# dmx2rgb.net
KiCad netlist of a schematic drawn in EAGLE
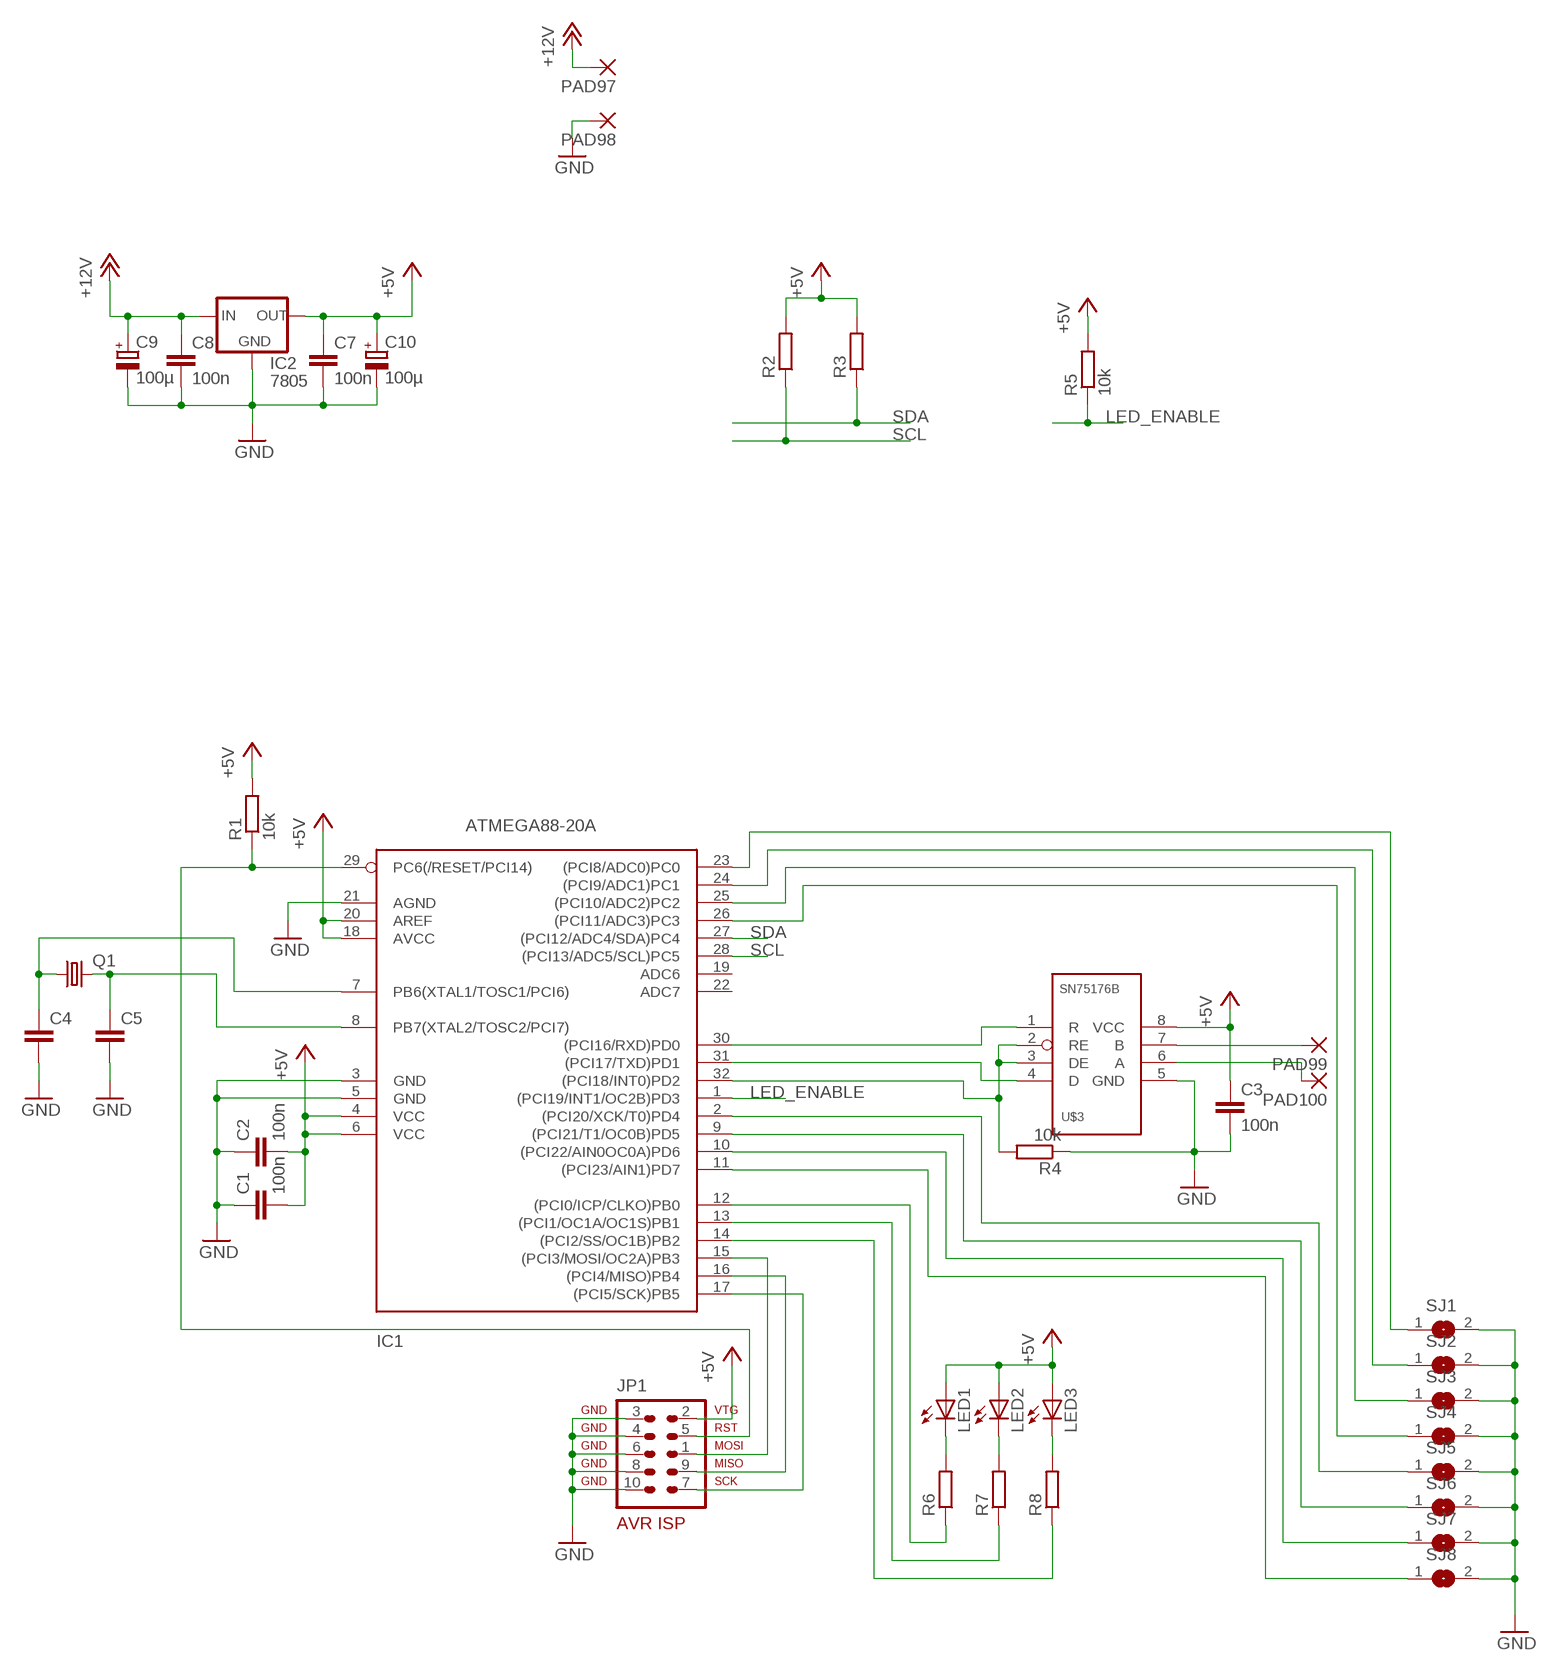
[diagram p0: schematic, sheet 1, part 1 of 2]
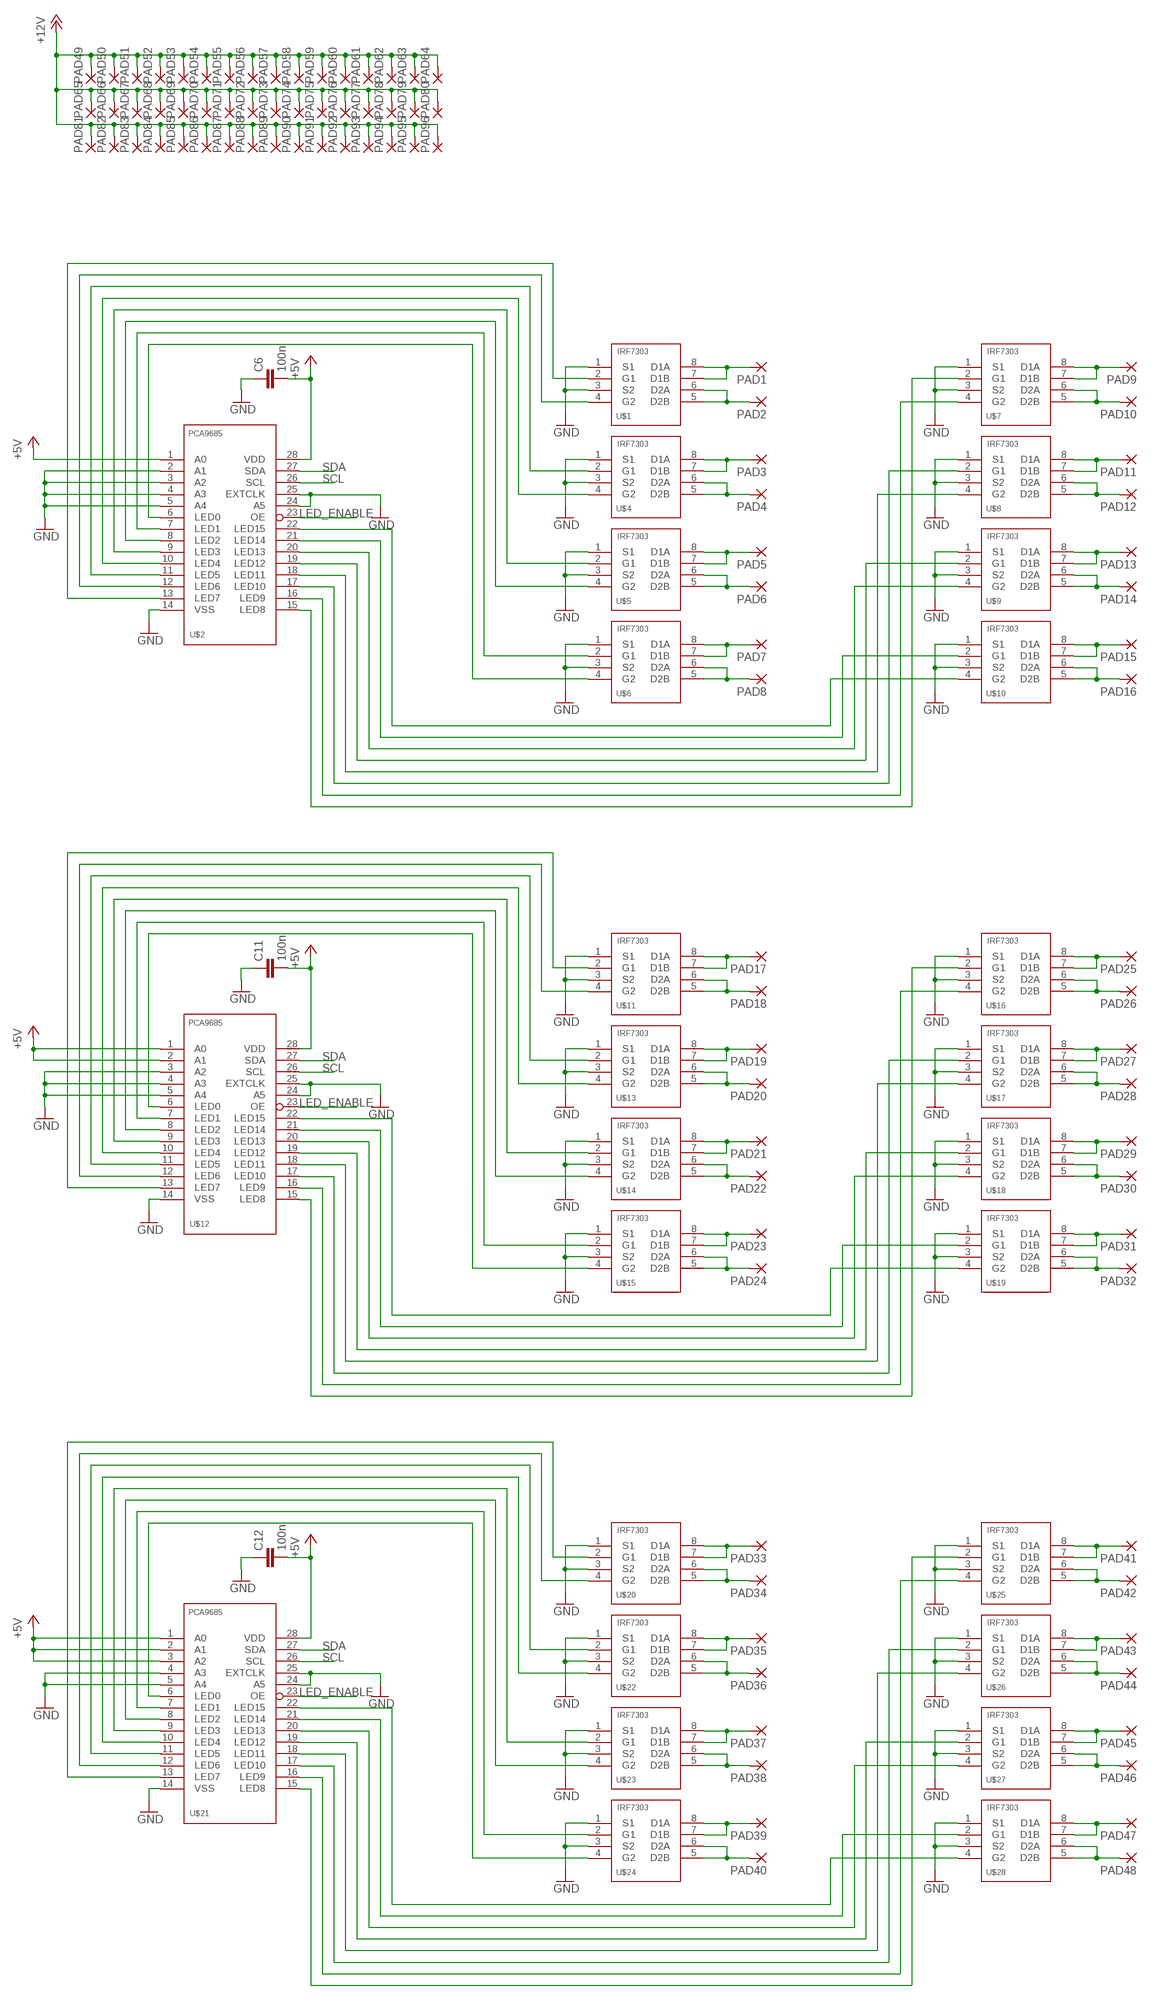
[diagram p1: schematic, sheet 1, part 2 of 2]

(export (version "E")
  (design (tool "Eeschema 10.0.6"))
  (components
    (comp (ref "C1")
      (value "100n")
      (footprint "eagle-import:CHIP_0805")
      (libsource (lib "eagle-import") (part "C0805"))
    )
    (comp (ref "C2")
      (value "100n")
      (footprint "eagle-import:CHIP_0805")
      (libsource (lib "eagle-import") (part "C0805"))
    )
    (comp (ref "C3")
      (value "100n")
      (footprint "eagle-import:CHIP_0805")
      (libsource (lib "eagle-import") (part "C0805"))
    )
    (comp (ref "C4")
      (value "C0805")
      (footprint "eagle-import:CHIP_0805")
      (libsource (lib "eagle-import") (part "C0805"))
    )
    (comp (ref "C5")
      (value "C0805")
      (footprint "eagle-import:CHIP_0805")
      (libsource (lib "eagle-import") (part "C0805"))
    )
    (comp (ref "C6")
      (value "100n")
      (footprint "eagle-import:CHIP_0805")
      (libsource (lib "eagle-import") (part "C0805"))
    )
    (comp (ref "C7")
      (value "100n")
      (footprint "eagle-import:CHIP_0805")
      (libsource (lib "eagle-import") (part "C0805"))
    )
    (comp (ref "C8")
      (value "100n")
      (footprint "eagle-import:CHIP_0805")
      (libsource (lib "eagle-import") (part "C0805"))
    )
    (comp (ref "C9")
      (value "100µ")
      (footprint "eagle-import:E2,5-7")
      (libsource (lib "eagle-import") (part "CPOL-EUE2.5-7"))
    )
    (comp (ref "C10")
      (value "100µ")
      (footprint "eagle-import:E2,5-7")
      (libsource (lib "eagle-import") (part "CPOL-EUE2.5-7"))
    )
    (comp (ref "C11")
      (value "100n")
      (footprint "eagle-import:CHIP_0805")
      (libsource (lib "eagle-import") (part "C0805"))
    )
    (comp (ref "C12")
      (value "100n")
      (footprint "eagle-import:CHIP_0805")
      (libsource (lib "eagle-import") (part "C0805"))
    )
    (comp (ref "IC1")
      (value "ATMEGA88-20A")
      (footprint "eagle-import:TQFP32-08")
      (libsource (lib "eagle-import") (part "ATMEGA88A-20"))
    )
    (comp (ref "IC2")
      (value "7805")
      (footprint "eagle-import:78LXX")
      (libsource (lib "eagle-import") (part "78LXX"))
    )
    (comp (ref "JP1")
      (value "AVR-ISP-10")
      (footprint "eagle-import:AVR-ISP-10")
      (libsource (lib "eagle-import") (part "AVR-ISP-10"))
    )
    (comp (ref "LED1")
      (value "LEDCHIPLED_0805")
      (footprint "eagle-import:CHIPLED_0805")
      (libsource (lib "eagle-import") (part "LEDCHIPLED_0805"))
    )
    (comp (ref "LED2")
      (value "LEDCHIPLED_0805")
      (footprint "eagle-import:CHIPLED_0805")
      (libsource (lib "eagle-import") (part "LEDCHIPLED_0805"))
    )
    (comp (ref "LED3")
      (value "LEDCHIPLED_0805")
      (footprint "eagle-import:CHIPLED_0805")
      (libsource (lib "eagle-import") (part "LEDCHIPLED_0805"))
    )
    (comp (ref "PAD1")
      (value "SMD_PAD_LONG")
      (footprint "eagle-import:SMD_PAD_LONG")
      (libsource (lib "eagle-import") (part "SMD_PAD_LONG"))
    )
    (comp (ref "PAD2")
      (value "SMD_PAD_LONG")
      (footprint "eagle-import:SMD_PAD_LONG")
      (libsource (lib "eagle-import") (part "SMD_PAD_LONG"))
    )
    (comp (ref "PAD3")
      (value "SMD_PAD_LONG")
      (footprint "eagle-import:SMD_PAD_LONG")
      (libsource (lib "eagle-import") (part "SMD_PAD_LONG"))
    )
    (comp (ref "PAD4")
      (value "SMD_PAD_LONG")
      (footprint "eagle-import:SMD_PAD_LONG")
      (libsource (lib "eagle-import") (part "SMD_PAD_LONG"))
    )
    (comp (ref "PAD5")
      (value "SMD_PAD_LONG")
      (footprint "eagle-import:SMD_PAD_LONG")
      (libsource (lib "eagle-import") (part "SMD_PAD_LONG"))
    )
    (comp (ref "PAD6")
      (value "SMD_PAD_LONG")
      (footprint "eagle-import:SMD_PAD_LONG")
      (libsource (lib "eagle-import") (part "SMD_PAD_LONG"))
    )
    (comp (ref "PAD7")
      (value "SMD_PAD_LONG")
      (footprint "eagle-import:SMD_PAD_LONG")
      (libsource (lib "eagle-import") (part "SMD_PAD_LONG"))
    )
    (comp (ref "PAD8")
      (value "SMD_PAD_LONG")
      (footprint "eagle-import:SMD_PAD_LONG")
      (libsource (lib "eagle-import") (part "SMD_PAD_LONG"))
    )
    (comp (ref "PAD9")
      (value "SMD_PAD_LONG")
      (footprint "eagle-import:SMD_PAD_LONG")
      (libsource (lib "eagle-import") (part "SMD_PAD_LONG"))
    )
    (comp (ref "PAD10")
      (value "SMD_PAD_LONG")
      (footprint "eagle-import:SMD_PAD_LONG")
      (libsource (lib "eagle-import") (part "SMD_PAD_LONG"))
    )
    (comp (ref "PAD11")
      (value "SMD_PAD_LONG")
      (footprint "eagle-import:SMD_PAD_LONG")
      (libsource (lib "eagle-import") (part "SMD_PAD_LONG"))
    )
    (comp (ref "PAD12")
      (value "SMD_PAD_LONG")
      (footprint "eagle-import:SMD_PAD_LONG")
      (libsource (lib "eagle-import") (part "SMD_PAD_LONG"))
    )
    (comp (ref "PAD13")
      (value "SMD_PAD_LONG")
      (footprint "eagle-import:SMD_PAD_LONG")
      (libsource (lib "eagle-import") (part "SMD_PAD_LONG"))
    )
    (comp (ref "PAD14")
      (value "SMD_PAD_LONG")
      (footprint "eagle-import:SMD_PAD_LONG")
      (libsource (lib "eagle-import") (part "SMD_PAD_LONG"))
    )
    (comp (ref "PAD15")
      (value "SMD_PAD_LONG")
      (footprint "eagle-import:SMD_PAD_LONG")
      (libsource (lib "eagle-import") (part "SMD_PAD_LONG"))
    )
    (comp (ref "PAD16")
      (value "SMD_PAD_LONG")
      (footprint "eagle-import:SMD_PAD_LONG")
      (libsource (lib "eagle-import") (part "SMD_PAD_LONG"))
    )
    (comp (ref "PAD17")
      (value "SMD_PAD_LONG")
      (footprint "eagle-import:SMD_PAD_LONG")
      (libsource (lib "eagle-import") (part "SMD_PAD_LONG"))
    )
    (comp (ref "PAD18")
      (value "SMD_PAD_LONG")
      (footprint "eagle-import:SMD_PAD_LONG")
      (libsource (lib "eagle-import") (part "SMD_PAD_LONG"))
    )
    (comp (ref "PAD19")
      (value "SMD_PAD_LONG")
      (footprint "eagle-import:SMD_PAD_LONG")
      (libsource (lib "eagle-import") (part "SMD_PAD_LONG"))
    )
    (comp (ref "PAD20")
      (value "SMD_PAD_LONG")
      (footprint "eagle-import:SMD_PAD_LONG")
      (libsource (lib "eagle-import") (part "SMD_PAD_LONG"))
    )
    (comp (ref "PAD21")
      (value "SMD_PAD_LONG")
      (footprint "eagle-import:SMD_PAD_LONG")
      (libsource (lib "eagle-import") (part "SMD_PAD_LONG"))
    )
    (comp (ref "PAD22")
      (value "SMD_PAD_LONG")
      (footprint "eagle-import:SMD_PAD_LONG")
      (libsource (lib "eagle-import") (part "SMD_PAD_LONG"))
    )
    (comp (ref "PAD23")
      (value "SMD_PAD_LONG")
      (footprint "eagle-import:SMD_PAD_LONG")
      (libsource (lib "eagle-import") (part "SMD_PAD_LONG"))
    )
    (comp (ref "PAD24")
      (value "SMD_PAD_LONG")
      (footprint "eagle-import:SMD_PAD_LONG")
      (libsource (lib "eagle-import") (part "SMD_PAD_LONG"))
    )
    (comp (ref "PAD25")
      (value "SMD_PAD_LONG")
      (footprint "eagle-import:SMD_PAD_LONG")
      (libsource (lib "eagle-import") (part "SMD_PAD_LONG"))
    )
    (comp (ref "PAD26")
      (value "SMD_PAD_LONG")
      (footprint "eagle-import:SMD_PAD_LONG")
      (libsource (lib "eagle-import") (part "SMD_PAD_LONG"))
    )
    (comp (ref "PAD27")
      (value "SMD_PAD_LONG")
      (footprint "eagle-import:SMD_PAD_LONG")
      (libsource (lib "eagle-import") (part "SMD_PAD_LONG"))
    )
    (comp (ref "PAD28")
      (value "SMD_PAD_LONG")
      (footprint "eagle-import:SMD_PAD_LONG")
      (libsource (lib "eagle-import") (part "SMD_PAD_LONG"))
    )
    (comp (ref "PAD29")
      (value "SMD_PAD_LONG")
      (footprint "eagle-import:SMD_PAD_LONG")
      (libsource (lib "eagle-import") (part "SMD_PAD_LONG"))
    )
    (comp (ref "PAD30")
      (value "SMD_PAD_LONG")
      (footprint "eagle-import:SMD_PAD_LONG")
      (libsource (lib "eagle-import") (part "SMD_PAD_LONG"))
    )
    (comp (ref "PAD31")
      (value "SMD_PAD_LONG")
      (footprint "eagle-import:SMD_PAD_LONG")
      (libsource (lib "eagle-import") (part "SMD_PAD_LONG"))
    )
    (comp (ref "PAD32")
      (value "SMD_PAD_LONG")
      (footprint "eagle-import:SMD_PAD_LONG")
      (libsource (lib "eagle-import") (part "SMD_PAD_LONG"))
    )
    (comp (ref "PAD33")
      (value "SMD_PAD_LONG")
      (footprint "eagle-import:SMD_PAD_LONG")
      (libsource (lib "eagle-import") (part "SMD_PAD_LONG"))
    )
    (comp (ref "PAD34")
      (value "SMD_PAD_LONG")
      (footprint "eagle-import:SMD_PAD_LONG")
      (libsource (lib "eagle-import") (part "SMD_PAD_LONG"))
    )
    (comp (ref "PAD35")
      (value "SMD_PAD_LONG")
      (footprint "eagle-import:SMD_PAD_LONG")
      (libsource (lib "eagle-import") (part "SMD_PAD_LONG"))
    )
    (comp (ref "PAD36")
      (value "SMD_PAD_LONG")
      (footprint "eagle-import:SMD_PAD_LONG")
      (libsource (lib "eagle-import") (part "SMD_PAD_LONG"))
    )
    (comp (ref "PAD37")
      (value "SMD_PAD_LONG")
      (footprint "eagle-import:SMD_PAD_LONG")
      (libsource (lib "eagle-import") (part "SMD_PAD_LONG"))
    )
    (comp (ref "PAD38")
      (value "SMD_PAD_LONG")
      (footprint "eagle-import:SMD_PAD_LONG")
      (libsource (lib "eagle-import") (part "SMD_PAD_LONG"))
    )
    (comp (ref "PAD39")
      (value "SMD_PAD_LONG")
      (footprint "eagle-import:SMD_PAD_LONG")
      (libsource (lib "eagle-import") (part "SMD_PAD_LONG"))
    )
    (comp (ref "PAD40")
      (value "SMD_PAD_LONG")
      (footprint "eagle-import:SMD_PAD_LONG")
      (libsource (lib "eagle-import") (part "SMD_PAD_LONG"))
    )
    (comp (ref "PAD41")
      (value "SMD_PAD_LONG")
      (footprint "eagle-import:SMD_PAD_LONG")
      (libsource (lib "eagle-import") (part "SMD_PAD_LONG"))
    )
    (comp (ref "PAD42")
      (value "SMD_PAD_LONG")
      (footprint "eagle-import:SMD_PAD_LONG")
      (libsource (lib "eagle-import") (part "SMD_PAD_LONG"))
    )
    (comp (ref "PAD43")
      (value "SMD_PAD_LONG")
      (footprint "eagle-import:SMD_PAD_LONG")
      (libsource (lib "eagle-import") (part "SMD_PAD_LONG"))
    )
    (comp (ref "PAD44")
      (value "SMD_PAD_LONG")
      (footprint "eagle-import:SMD_PAD_LONG")
      (libsource (lib "eagle-import") (part "SMD_PAD_LONG"))
    )
    (comp (ref "PAD45")
      (value "SMD_PAD_LONG")
      (footprint "eagle-import:SMD_PAD_LONG")
      (libsource (lib "eagle-import") (part "SMD_PAD_LONG"))
    )
    (comp (ref "PAD46")
      (value "SMD_PAD_LONG")
      (footprint "eagle-import:SMD_PAD_LONG")
      (libsource (lib "eagle-import") (part "SMD_PAD_LONG"))
    )
    (comp (ref "PAD47")
      (value "SMD_PAD_LONG")
      (footprint "eagle-import:SMD_PAD_LONG")
      (libsource (lib "eagle-import") (part "SMD_PAD_LONG"))
    )
    (comp (ref "PAD48")
      (value "SMD_PAD_LONG")
      (footprint "eagle-import:SMD_PAD_LONG")
      (libsource (lib "eagle-import") (part "SMD_PAD_LONG"))
    )
    (comp (ref "PAD49")
      (value "SMD_PAD_LONG")
      (footprint "eagle-import:SMD_PAD_LONG")
      (libsource (lib "eagle-import") (part "SMD_PAD_LONG"))
    )
    (comp (ref "PAD50")
      (value "SMD_PAD_LONG")
      (footprint "eagle-import:SMD_PAD_LONG")
      (libsource (lib "eagle-import") (part "SMD_PAD_LONG"))
    )
    (comp (ref "PAD51")
      (value "SMD_PAD_LONG")
      (footprint "eagle-import:SMD_PAD_LONG")
      (libsource (lib "eagle-import") (part "SMD_PAD_LONG"))
    )
    (comp (ref "PAD52")
      (value "SMD_PAD_LONG")
      (footprint "eagle-import:SMD_PAD_LONG")
      (libsource (lib "eagle-import") (part "SMD_PAD_LONG"))
    )
    (comp (ref "PAD53")
      (value "SMD_PAD_LONG")
      (footprint "eagle-import:SMD_PAD_LONG")
      (libsource (lib "eagle-import") (part "SMD_PAD_LONG"))
    )
    (comp (ref "PAD54")
      (value "SMD_PAD_LONG")
      (footprint "eagle-import:SMD_PAD_LONG")
      (libsource (lib "eagle-import") (part "SMD_PAD_LONG"))
    )
    (comp (ref "PAD55")
      (value "SMD_PAD_LONG")
      (footprint "eagle-import:SMD_PAD_LONG")
      (libsource (lib "eagle-import") (part "SMD_PAD_LONG"))
    )
    (comp (ref "PAD56")
      (value "SMD_PAD_LONG")
      (footprint "eagle-import:SMD_PAD_LONG")
      (libsource (lib "eagle-import") (part "SMD_PAD_LONG"))
    )
    (comp (ref "PAD57")
      (value "SMD_PAD_LONG")
      (footprint "eagle-import:SMD_PAD_LONG")
      (libsource (lib "eagle-import") (part "SMD_PAD_LONG"))
    )
    (comp (ref "PAD58")
      (value "SMD_PAD_LONG")
      (footprint "eagle-import:SMD_PAD_LONG")
      (libsource (lib "eagle-import") (part "SMD_PAD_LONG"))
    )
    (comp (ref "PAD59")
      (value "SMD_PAD_LONG")
      (footprint "eagle-import:SMD_PAD_LONG")
      (libsource (lib "eagle-import") (part "SMD_PAD_LONG"))
    )
    (comp (ref "PAD60")
      (value "SMD_PAD_LONG")
      (footprint "eagle-import:SMD_PAD_LONG")
      (libsource (lib "eagle-import") (part "SMD_PAD_LONG"))
    )
    (comp (ref "PAD61")
      (value "SMD_PAD_LONG")
      (footprint "eagle-import:SMD_PAD_LONG")
      (libsource (lib "eagle-import") (part "SMD_PAD_LONG"))
    )
    (comp (ref "PAD62")
      (value "SMD_PAD_LONG")
      (footprint "eagle-import:SMD_PAD_LONG")
      (libsource (lib "eagle-import") (part "SMD_PAD_LONG"))
    )
    (comp (ref "PAD63")
      (value "SMD_PAD_LONG")
      (footprint "eagle-import:SMD_PAD_LONG")
      (libsource (lib "eagle-import") (part "SMD_PAD_LONG"))
    )
    (comp (ref "PAD64")
      (value "SMD_PAD_LONG")
      (footprint "eagle-import:SMD_PAD_LONG")
      (libsource (lib "eagle-import") (part "SMD_PAD_LONG"))
    )
    (comp (ref "PAD65")
      (value "SMD_PAD_LONG")
      (footprint "eagle-import:SMD_PAD_LONG")
      (libsource (lib "eagle-import") (part "SMD_PAD_LONG"))
    )
    (comp (ref "PAD66")
      (value "SMD_PAD_LONG")
      (footprint "eagle-import:SMD_PAD_LONG")
      (libsource (lib "eagle-import") (part "SMD_PAD_LONG"))
    )
    (comp (ref "PAD67")
      (value "SMD_PAD_LONG")
      (footprint "eagle-import:SMD_PAD_LONG")
      (libsource (lib "eagle-import") (part "SMD_PAD_LONG"))
    )
    (comp (ref "PAD68")
      (value "SMD_PAD_LONG")
      (footprint "eagle-import:SMD_PAD_LONG")
      (libsource (lib "eagle-import") (part "SMD_PAD_LONG"))
    )
    (comp (ref "PAD69")
      (value "SMD_PAD_LONG")
      (footprint "eagle-import:SMD_PAD_LONG")
      (libsource (lib "eagle-import") (part "SMD_PAD_LONG"))
    )
    (comp (ref "PAD70")
      (value "SMD_PAD_LONG")
      (footprint "eagle-import:SMD_PAD_LONG")
      (libsource (lib "eagle-import") (part "SMD_PAD_LONG"))
    )
    (comp (ref "PAD71")
      (value "SMD_PAD_LONG")
      (footprint "eagle-import:SMD_PAD_LONG")
      (libsource (lib "eagle-import") (part "SMD_PAD_LONG"))
    )
    (comp (ref "PAD72")
      (value "SMD_PAD_LONG")
      (footprint "eagle-import:SMD_PAD_LONG")
      (libsource (lib "eagle-import") (part "SMD_PAD_LONG"))
    )
    (comp (ref "PAD73")
      (value "SMD_PAD_LONG")
      (footprint "eagle-import:SMD_PAD_LONG")
      (libsource (lib "eagle-import") (part "SMD_PAD_LONG"))
    )
    (comp (ref "PAD74")
      (value "SMD_PAD_LONG")
      (footprint "eagle-import:SMD_PAD_LONG")
      (libsource (lib "eagle-import") (part "SMD_PAD_LONG"))
    )
    (comp (ref "PAD75")
      (value "SMD_PAD_LONG")
      (footprint "eagle-import:SMD_PAD_LONG")
      (libsource (lib "eagle-import") (part "SMD_PAD_LONG"))
    )
    (comp (ref "PAD76")
      (value "SMD_PAD_LONG")
      (footprint "eagle-import:SMD_PAD_LONG")
      (libsource (lib "eagle-import") (part "SMD_PAD_LONG"))
    )
    (comp (ref "PAD77")
      (value "SMD_PAD_LONG")
      (footprint "eagle-import:SMD_PAD_LONG")
      (libsource (lib "eagle-import") (part "SMD_PAD_LONG"))
    )
    (comp (ref "PAD78")
      (value "SMD_PAD_LONG")
      (footprint "eagle-import:SMD_PAD_LONG")
      (libsource (lib "eagle-import") (part "SMD_PAD_LONG"))
    )
    (comp (ref "PAD79")
      (value "SMD_PAD_LONG")
      (footprint "eagle-import:SMD_PAD_LONG")
      (libsource (lib "eagle-import") (part "SMD_PAD_LONG"))
    )
    (comp (ref "PAD80")
      (value "SMD_PAD_LONG")
      (footprint "eagle-import:SMD_PAD_LONG")
      (libsource (lib "eagle-import") (part "SMD_PAD_LONG"))
    )
    (comp (ref "PAD81")
      (value "SMD_PAD_LONG")
      (footprint "eagle-import:SMD_PAD_LONG")
      (libsource (lib "eagle-import") (part "SMD_PAD_LONG"))
    )
    (comp (ref "PAD82")
      (value "SMD_PAD_LONG")
      (footprint "eagle-import:SMD_PAD_LONG")
      (libsource (lib "eagle-import") (part "SMD_PAD_LONG"))
    )
    (comp (ref "PAD83")
      (value "SMD_PAD_LONG")
      (footprint "eagle-import:SMD_PAD_LONG")
      (libsource (lib "eagle-import") (part "SMD_PAD_LONG"))
    )
    (comp (ref "PAD84")
      (value "SMD_PAD_LONG")
      (footprint "eagle-import:SMD_PAD_LONG")
      (libsource (lib "eagle-import") (part "SMD_PAD_LONG"))
    )
    (comp (ref "PAD85")
      (value "SMD_PAD_LONG")
      (footprint "eagle-import:SMD_PAD_LONG")
      (libsource (lib "eagle-import") (part "SMD_PAD_LONG"))
    )
    (comp (ref "PAD86")
      (value "SMD_PAD_LONG")
      (footprint "eagle-import:SMD_PAD_LONG")
      (libsource (lib "eagle-import") (part "SMD_PAD_LONG"))
    )
    (comp (ref "PAD87")
      (value "SMD_PAD_LONG")
      (footprint "eagle-import:SMD_PAD_LONG")
      (libsource (lib "eagle-import") (part "SMD_PAD_LONG"))
    )
    (comp (ref "PAD88")
      (value "SMD_PAD_LONG")
      (footprint "eagle-import:SMD_PAD_LONG")
      (libsource (lib "eagle-import") (part "SMD_PAD_LONG"))
    )
    (comp (ref "PAD89")
      (value "SMD_PAD_LONG")
      (footprint "eagle-import:SMD_PAD_LONG")
      (libsource (lib "eagle-import") (part "SMD_PAD_LONG"))
    )
    (comp (ref "PAD90")
      (value "SMD_PAD_LONG")
      (footprint "eagle-import:SMD_PAD_LONG")
      (libsource (lib "eagle-import") (part "SMD_PAD_LONG"))
    )
    (comp (ref "PAD91")
      (value "SMD_PAD_LONG")
      (footprint "eagle-import:SMD_PAD_LONG")
      (libsource (lib "eagle-import") (part "SMD_PAD_LONG"))
    )
    (comp (ref "PAD92")
      (value "SMD_PAD_LONG")
      (footprint "eagle-import:SMD_PAD_LONG")
      (libsource (lib "eagle-import") (part "SMD_PAD_LONG"))
    )
    (comp (ref "PAD93")
      (value "SMD_PAD_LONG")
      (footprint "eagle-import:SMD_PAD_LONG")
      (libsource (lib "eagle-import") (part "SMD_PAD_LONG"))
    )
    (comp (ref "PAD94")
      (value "SMD_PAD_LONG")
      (footprint "eagle-import:SMD_PAD_LONG")
      (libsource (lib "eagle-import") (part "SMD_PAD_LONG"))
    )
    (comp (ref "PAD95")
      (value "SMD_PAD_LONG")
      (footprint "eagle-import:SMD_PAD_LONG")
      (libsource (lib "eagle-import") (part "SMD_PAD_LONG"))
    )
    (comp (ref "PAD96")
      (value "SMD_PAD_LONG")
      (footprint "eagle-import:SMD_PAD_LONG")
      (libsource (lib "eagle-import") (part "SMD_PAD_LONG"))
    )
    (comp (ref "PAD97")
      (value "SMD5")
      (footprint "eagle-import:SMD2,54-5,08")
      (libsource (lib "eagle-import") (part "SMD5"))
    )
    (comp (ref "PAD98")
      (value "SMD5")
      (footprint "eagle-import:SMD2,54-5,08")
      (libsource (lib "eagle-import") (part "SMD5"))
    )
    (comp (ref "PAD99")
      (value "SMD_PAD_LONG")
      (footprint "eagle-import:SMD_PAD_LONG")
      (libsource (lib "eagle-import") (part "SMD_PAD_LONG"))
    )
    (comp (ref "PAD100")
      (value "SMD_PAD_LONG")
      (footprint "eagle-import:SMD_PAD_LONG")
      (libsource (lib "eagle-import") (part "SMD_PAD_LONG"))
    )
    (comp (ref "Q1")
      (value "CRYSTAL49")
      (footprint "eagle-import:HC49_S")
      (libsource (lib "eagle-import") (part "CRYSTAL49"))
    )
    (comp (ref "R1")
      (value "10k")
      (footprint "eagle-import:CHIP_0805")
      (libsource (lib "eagle-import") (part "R0805"))
    )
    (comp (ref "R2")
      (value "R0805")
      (footprint "eagle-import:CHIP_0805")
      (libsource (lib "eagle-import") (part "R0805"))
    )
    (comp (ref "R3")
      (value "R0805")
      (footprint "eagle-import:CHIP_0805")
      (libsource (lib "eagle-import") (part "R0805"))
    )
    (comp (ref "R4")
      (value "10k")
      (footprint "eagle-import:CHIP_0805")
      (libsource (lib "eagle-import") (part "R0805"))
    )
    (comp (ref "R5")
      (value "10k")
      (footprint "eagle-import:CHIP_0805")
      (libsource (lib "eagle-import") (part "R0805"))
    )
    (comp (ref "R6")
      (value "R0805")
      (footprint "eagle-import:CHIP_0805")
      (libsource (lib "eagle-import") (part "R0805"))
    )
    (comp (ref "R7")
      (value "R0805")
      (footprint "eagle-import:CHIP_0805")
      (libsource (lib "eagle-import") (part "R0805"))
    )
    (comp (ref "R8")
      (value "R0805")
      (footprint "eagle-import:CHIP_0805")
      (libsource (lib "eagle-import") (part "R0805"))
    )
    (comp (ref "SJ1") (value "SJ") (footprint "eagle-import:SJ") (libsource (lib "eagle-import") (part "SJ")))
    (comp (ref "SJ2") (value "SJ") (footprint "eagle-import:SJ") (libsource (lib "eagle-import") (part "SJ")))
    (comp (ref "SJ3") (value "SJ") (footprint "eagle-import:SJ") (libsource (lib "eagle-import") (part "SJ")))
    (comp (ref "SJ4") (value "SJ") (footprint "eagle-import:SJ") (libsource (lib "eagle-import") (part "SJ")))
    (comp (ref "SJ5") (value "SJ") (footprint "eagle-import:SJ") (libsource (lib "eagle-import") (part "SJ")))
    (comp (ref "SJ6") (value "SJ") (footprint "eagle-import:SJ") (libsource (lib "eagle-import") (part "SJ")))
    (comp (ref "SJ7") (value "SJ") (footprint "eagle-import:SJ") (libsource (lib "eagle-import") (part "SJ")))
    (comp (ref "SJ8") (value "SJ") (footprint "eagle-import:SJ") (libsource (lib "eagle-import") (part "SJ")))
    (comp (ref "U$1")
      (value "IRF7303")
      (footprint "eagle-import:SO8")
      (libsource (lib "eagle-import") (part "IRF7303"))
    )
    (comp (ref "U$2")
      (value "PCA9685")
      (footprint "eagle-import:TSSOP28")
      (libsource (lib "eagle-import") (part "PCA9685"))
    )
    (comp (ref "U$3")
      (value "SN75176B")
      (footprint "eagle-import:SO8")
      (libsource (lib "eagle-import") (part "SN75176B"))
    )
    (comp (ref "U$4")
      (value "IRF7303")
      (footprint "eagle-import:SO8")
      (libsource (lib "eagle-import") (part "IRF7303"))
    )
    (comp (ref "U$5")
      (value "IRF7303")
      (footprint "eagle-import:SO8")
      (libsource (lib "eagle-import") (part "IRF7303"))
    )
    (comp (ref "U$6")
      (value "IRF7303")
      (footprint "eagle-import:SO8")
      (libsource (lib "eagle-import") (part "IRF7303"))
    )
    (comp (ref "U$7")
      (value "IRF7303")
      (footprint "eagle-import:SO8")
      (libsource (lib "eagle-import") (part "IRF7303"))
    )
    (comp (ref "U$8")
      (value "IRF7303")
      (footprint "eagle-import:SO8")
      (libsource (lib "eagle-import") (part "IRF7303"))
    )
    (comp (ref "U$9")
      (value "IRF7303")
      (footprint "eagle-import:SO8")
      (libsource (lib "eagle-import") (part "IRF7303"))
    )
    (comp (ref "U$10")
      (value "IRF7303")
      (footprint "eagle-import:SO8")
      (libsource (lib "eagle-import") (part "IRF7303"))
    )
    (comp (ref "U$11")
      (value "IRF7303")
      (footprint "eagle-import:SO8")
      (libsource (lib "eagle-import") (part "IRF7303"))
    )
    (comp (ref "U$12")
      (value "PCA9685")
      (footprint "eagle-import:TSSOP28")
      (libsource (lib "eagle-import") (part "PCA9685"))
    )
    (comp (ref "U$13")
      (value "IRF7303")
      (footprint "eagle-import:SO8")
      (libsource (lib "eagle-import") (part "IRF7303"))
    )
    (comp (ref "U$14")
      (value "IRF7303")
      (footprint "eagle-import:SO8")
      (libsource (lib "eagle-import") (part "IRF7303"))
    )
    (comp (ref "U$15")
      (value "IRF7303")
      (footprint "eagle-import:SO8")
      (libsource (lib "eagle-import") (part "IRF7303"))
    )
    (comp (ref "U$16")
      (value "IRF7303")
      (footprint "eagle-import:SO8")
      (libsource (lib "eagle-import") (part "IRF7303"))
    )
    (comp (ref "U$17")
      (value "IRF7303")
      (footprint "eagle-import:SO8")
      (libsource (lib "eagle-import") (part "IRF7303"))
    )
    (comp (ref "U$18")
      (value "IRF7303")
      (footprint "eagle-import:SO8")
      (libsource (lib "eagle-import") (part "IRF7303"))
    )
    (comp (ref "U$19")
      (value "IRF7303")
      (footprint "eagle-import:SO8")
      (libsource (lib "eagle-import") (part "IRF7303"))
    )
    (comp (ref "U$20")
      (value "IRF7303")
      (footprint "eagle-import:SO8")
      (libsource (lib "eagle-import") (part "IRF7303"))
    )
    (comp (ref "U$21")
      (value "PCA9685")
      (footprint "eagle-import:TSSOP28")
      (libsource (lib "eagle-import") (part "PCA9685"))
    )
    (comp (ref "U$22")
      (value "IRF7303")
      (footprint "eagle-import:SO8")
      (libsource (lib "eagle-import") (part "IRF7303"))
    )
    (comp (ref "U$23")
      (value "IRF7303")
      (footprint "eagle-import:SO8")
      (libsource (lib "eagle-import") (part "IRF7303"))
    )
    (comp (ref "U$24")
      (value "IRF7303")
      (footprint "eagle-import:SO8")
      (libsource (lib "eagle-import") (part "IRF7303"))
    )
    (comp (ref "U$25")
      (value "IRF7303")
      (footprint "eagle-import:SO8")
      (libsource (lib "eagle-import") (part "IRF7303"))
    )
    (comp (ref "U$26")
      (value "IRF7303")
      (footprint "eagle-import:SO8")
      (libsource (lib "eagle-import") (part "IRF7303"))
    )
    (comp (ref "U$27")
      (value "IRF7303")
      (footprint "eagle-import:SO8")
      (libsource (lib "eagle-import") (part "IRF7303"))
    )
    (comp (ref "U$28")
      (value "IRF7303")
      (footprint "eagle-import:SO8")
      (libsource (lib "eagle-import") (part "IRF7303"))
    )
  )
  (nets
    (net (code "1") (name "+5V") (class "Default")
      (node (ref "C1") (pin "2") (pinfunction "2_2") (pintype "passive"))
      (node (ref "C10") (pin "+") (pinfunction "+_+") (pintype "passive"))
      (node (ref "C11") (pin "2") (pinfunction "2_2") (pintype "passive"))
      (node (ref "C12") (pin "2") (pinfunction "2_2") (pintype "passive"))
      (node (ref "C2") (pin "2") (pinfunction "2_2") (pintype "passive"))
      (node (ref "C3") (pin "1") (pinfunction "1_1") (pintype "passive"))
      (node (ref "C6") (pin "2") (pinfunction "2_2") (pintype "passive"))
      (node (ref "C7") (pin "1") (pinfunction "1_1") (pintype "passive"))
      (node (ref "IC1") (pin "18") (pinfunction "AVCC_18") (pintype "bidirectional"))
      (node (ref "IC1") (pin "20") (pinfunction "AREF_20") (pintype "bidirectional"))
      (node (ref "IC1") (pin "4") (pinfunction "VCC_4") (pintype "power_in"))
      (node (ref "IC1") (pin "6") (pinfunction "VCC_6") (pintype "power_in"))
      (node (ref "IC2") (pin "OUT") (pinfunction "OUT_OUT") (pintype "passive"))
      (node (ref "JP1") (pin "2") (pinfunction "2_2") (pintype "passive"))
      (node (ref "LED1") (pin "A") (pinfunction "A_A") (pintype "passive"))
      (node (ref "LED2") (pin "A") (pinfunction "A_A") (pintype "passive"))
      (node (ref "LED3") (pin "A") (pinfunction "A_A") (pintype "passive"))
      (node (ref "R1") (pin "2") (pinfunction "2_2") (pintype "passive"))
      (node (ref "R2") (pin "2") (pinfunction "2_2") (pintype "passive"))
      (node (ref "R3") (pin "2") (pinfunction "2_2") (pintype "passive"))
      (node (ref "R5") (pin "2") (pinfunction "2_2") (pintype "passive"))
      (node (ref "U$12") (pin "1") (pinfunction "A0_1") (pintype "bidirectional"))
      (node (ref "U$12") (pin "2") (pinfunction "A1_2") (pintype "bidirectional"))
      (node (ref "U$12") (pin "28") (pinfunction "VDD_28") (pintype "bidirectional"))
      (node (ref "U$2") (pin "1") (pinfunction "A0_1") (pintype "bidirectional"))
      (node (ref "U$2") (pin "28") (pinfunction "VDD_28") (pintype "bidirectional"))
      (node (ref "U$21") (pin "1") (pinfunction "A0_1") (pintype "bidirectional"))
      (node (ref "U$21") (pin "2") (pinfunction "A1_2") (pintype "bidirectional"))
      (node (ref "U$21") (pin "28") (pinfunction "VDD_28") (pintype "bidirectional"))
      (node (ref "U$21") (pin "3") (pinfunction "A2_3") (pintype "bidirectional"))
      (node (ref "U$3") (pin "8") (pinfunction "VCC_8") (pintype "bidirectional"))
    )
    (net (code "2") (name "+12V") (class "Default")
      (node (ref "C8") (pin "1") (pinfunction "1_1") (pintype "passive"))
      (node (ref "C9") (pin "+") (pinfunction "+_+") (pintype "passive"))
      (node (ref "IC2") (pin "IN") (pinfunction "IN_IN") (pintype "input"))
      (node (ref "PAD49") (pin "P$1") (pinfunction "P_P$1") (pintype "passive"))
      (node (ref "PAD50") (pin "P$1") (pinfunction "P_P$1") (pintype "passive"))
      (node (ref "PAD51") (pin "P$1") (pinfunction "P_P$1") (pintype "passive"))
      (node (ref "PAD52") (pin "P$1") (pinfunction "P_P$1") (pintype "passive"))
      (node (ref "PAD53") (pin "P$1") (pinfunction "P_P$1") (pintype "passive"))
      (node (ref "PAD54") (pin "P$1") (pinfunction "P_P$1") (pintype "passive"))
      (node (ref "PAD55") (pin "P$1") (pinfunction "P_P$1") (pintype "passive"))
      (node (ref "PAD56") (pin "P$1") (pinfunction "P_P$1") (pintype "passive"))
      (node (ref "PAD57") (pin "P$1") (pinfunction "P_P$1") (pintype "passive"))
      (node (ref "PAD58") (pin "P$1") (pinfunction "P_P$1") (pintype "passive"))
      (node (ref "PAD59") (pin "P$1") (pinfunction "P_P$1") (pintype "passive"))
      (node (ref "PAD60") (pin "P$1") (pinfunction "P_P$1") (pintype "passive"))
      (node (ref "PAD61") (pin "P$1") (pinfunction "P_P$1") (pintype "passive"))
      (node (ref "PAD62") (pin "P$1") (pinfunction "P_P$1") (pintype "passive"))
      (node (ref "PAD63") (pin "P$1") (pinfunction "P_P$1") (pintype "passive"))
      (node (ref "PAD64") (pin "P$1") (pinfunction "P_P$1") (pintype "passive"))
      (node (ref "PAD65") (pin "P$1") (pinfunction "P_P$1") (pintype "passive"))
      (node (ref "PAD66") (pin "P$1") (pinfunction "P_P$1") (pintype "passive"))
      (node (ref "PAD67") (pin "P$1") (pinfunction "P_P$1") (pintype "passive"))
      (node (ref "PAD68") (pin "P$1") (pinfunction "P_P$1") (pintype "passive"))
      (node (ref "PAD69") (pin "P$1") (pinfunction "P_P$1") (pintype "passive"))
      (node (ref "PAD70") (pin "P$1") (pinfunction "P_P$1") (pintype "passive"))
      (node (ref "PAD71") (pin "P$1") (pinfunction "P_P$1") (pintype "passive"))
      (node (ref "PAD72") (pin "P$1") (pinfunction "P_P$1") (pintype "passive"))
      (node (ref "PAD73") (pin "P$1") (pinfunction "P_P$1") (pintype "passive"))
      (node (ref "PAD74") (pin "P$1") (pinfunction "P_P$1") (pintype "passive"))
      (node (ref "PAD75") (pin "P$1") (pinfunction "P_P$1") (pintype "passive"))
      (node (ref "PAD76") (pin "P$1") (pinfunction "P_P$1") (pintype "passive"))
      (node (ref "PAD77") (pin "P$1") (pinfunction "P_P$1") (pintype "passive"))
      (node (ref "PAD78") (pin "P$1") (pinfunction "P_P$1") (pintype "passive"))
      (node (ref "PAD79") (pin "P$1") (pinfunction "P_P$1") (pintype "passive"))
      (node (ref "PAD80") (pin "P$1") (pinfunction "P_P$1") (pintype "passive"))
      (node (ref "PAD81") (pin "P$1") (pinfunction "P_P$1") (pintype "passive"))
      (node (ref "PAD82") (pin "P$1") (pinfunction "P_P$1") (pintype "passive"))
      (node (ref "PAD83") (pin "P$1") (pinfunction "P_P$1") (pintype "passive"))
      (node (ref "PAD84") (pin "P$1") (pinfunction "P_P$1") (pintype "passive"))
      (node (ref "PAD85") (pin "P$1") (pinfunction "P_P$1") (pintype "passive"))
      (node (ref "PAD86") (pin "P$1") (pinfunction "P_P$1") (pintype "passive"))
      (node (ref "PAD87") (pin "P$1") (pinfunction "P_P$1") (pintype "passive"))
      (node (ref "PAD88") (pin "P$1") (pinfunction "P_P$1") (pintype "passive"))
      (node (ref "PAD89") (pin "P$1") (pinfunction "P_P$1") (pintype "passive"))
      (node (ref "PAD90") (pin "P$1") (pinfunction "P_P$1") (pintype "passive"))
      (node (ref "PAD91") (pin "P$1") (pinfunction "P_P$1") (pintype "passive"))
      (node (ref "PAD92") (pin "P$1") (pinfunction "P_P$1") (pintype "passive"))
      (node (ref "PAD93") (pin "P$1") (pinfunction "P_P$1") (pintype "passive"))
      (node (ref "PAD94") (pin "P$1") (pinfunction "P_P$1") (pintype "passive"))
      (node (ref "PAD95") (pin "P$1") (pinfunction "P_P$1") (pintype "passive"))
      (node (ref "PAD96") (pin "P$1") (pinfunction "P_P$1") (pintype "passive"))
      (node (ref "PAD97") (pin "1") (pinfunction "P_1") (pintype "passive"))
    )
    (net (code "3") (name "/LED_ENABLE") (class "Default")
      (node (ref "IC1") (pin "1") (pinfunction "(PCI19/INT1/OC2B)PD3_1") (pintype "bidirectional"))
      (node (ref "R5") (pin "1") (pinfunction "1_1") (pintype "passive"))
      (node (ref "U$12") (pin "23") (pinfunction "OE_23") (pintype "input"))
      (node (ref "U$2") (pin "23") (pinfunction "OE_23") (pintype "input"))
      (node (ref "U$21") (pin "23") (pinfunction "OE_23") (pintype "input"))
    )
    (net (code "4") (name "/SCL") (class "Default")
      (node (ref "IC1") (pin "28") (pinfunction "(PCI13/ADC5/SCL)PC5_28") (pintype "bidirectional"))
      (node (ref "R2") (pin "1") (pinfunction "1_1") (pintype "passive"))
      (node (ref "U$12") (pin "26") (pinfunction "SCL_26") (pintype "bidirectional"))
      (node (ref "U$2") (pin "26") (pinfunction "SCL_26") (pintype "bidirectional"))
      (node (ref "U$21") (pin "26") (pinfunction "SCL_26") (pintype "bidirectional"))
    )
    (net (code "5") (name "/SDA") (class "Default")
      (node (ref "IC1") (pin "27") (pinfunction "(PCI12/ADC4/SDA)PC4_27") (pintype "bidirectional"))
      (node (ref "R3") (pin "1") (pinfunction "1_1") (pintype "passive"))
      (node (ref "U$12") (pin "27") (pinfunction "SDA_27") (pintype "bidirectional"))
      (node (ref "U$2") (pin "27") (pinfunction "SDA_27") (pintype "bidirectional"))
      (node (ref "U$21") (pin "27") (pinfunction "SDA_27") (pintype "bidirectional"))
    )
    (net (code "6") (name "GND") (class "Default")
      (node (ref "C1") (pin "1") (pinfunction "1_1") (pintype "passive"))
      (node (ref "C10") (pin "-") (pinfunction "-_-") (pintype "passive"))
      (node (ref "C11") (pin "1") (pinfunction "1_1") (pintype "passive"))
      (node (ref "C12") (pin "1") (pinfunction "1_1") (pintype "passive"))
      (node (ref "C2") (pin "1") (pinfunction "1_1") (pintype "passive"))
      (node (ref "C3") (pin "2") (pinfunction "2_2") (pintype "passive"))
      (node (ref "C4") (pin "2") (pinfunction "2_2") (pintype "passive"))
      (node (ref "C5") (pin "2") (pinfunction "2_2") (pintype "passive"))
      (node (ref "C6") (pin "1") (pinfunction "1_1") (pintype "passive"))
      (node (ref "C7") (pin "2") (pinfunction "2_2") (pintype "passive"))
      (node (ref "C8") (pin "2") (pinfunction "2_2") (pintype "passive"))
      (node (ref "C9") (pin "-") (pinfunction "-_-") (pintype "passive"))
      (node (ref "IC1") (pin "21") (pinfunction "AGND_21") (pintype "bidirectional"))
      (node (ref "IC1") (pin "3") (pinfunction "GND_3") (pintype "power_in"))
      (node (ref "IC1") (pin "5") (pinfunction "GND_5") (pintype "power_in"))
      (node (ref "IC2") (pin "GND") (pinfunction "GND_GND") (pintype "input"))
      (node (ref "JP1") (pin "10") (pinfunction "10_10") (pintype "passive"))
      (node (ref "JP1") (pin "3") (pinfunction "3_3") (pintype "passive"))
      (node (ref "JP1") (pin "4") (pinfunction "4_4") (pintype "passive"))
      (node (ref "JP1") (pin "6") (pinfunction "6_6") (pintype "passive"))
      (node (ref "JP1") (pin "8") (pinfunction "8_8") (pintype "passive"))
      (node (ref "PAD98") (pin "1") (pinfunction "P_1") (pintype "passive"))
      (node (ref "R4") (pin "1") (pinfunction "1_1") (pintype "passive"))
      (node (ref "SJ1") (pin "2") (pinfunction "2_2") (pintype "passive"))
      (node (ref "SJ2") (pin "2") (pinfunction "2_2") (pintype "passive"))
      (node (ref "SJ3") (pin "2") (pinfunction "2_2") (pintype "passive"))
      (node (ref "SJ4") (pin "2") (pinfunction "2_2") (pintype "passive"))
      (node (ref "SJ5") (pin "2") (pinfunction "2_2") (pintype "passive"))
      (node (ref "SJ6") (pin "2") (pinfunction "2_2") (pintype "passive"))
      (node (ref "SJ7") (pin "2") (pinfunction "2_2") (pintype "passive"))
      (node (ref "SJ8") (pin "2") (pinfunction "2_2") (pintype "passive"))
      (node (ref "U$1") (pin "1") (pinfunction "S1_1") (pintype "input"))
      (node (ref "U$1") (pin "3") (pinfunction "S2_3") (pintype "bidirectional"))
      (node (ref "U$10") (pin "1") (pinfunction "S1_1") (pintype "input"))
      (node (ref "U$10") (pin "3") (pinfunction "S2_3") (pintype "bidirectional"))
      (node (ref "U$11") (pin "1") (pinfunction "S1_1") (pintype "input"))
      (node (ref "U$11") (pin "3") (pinfunction "S2_3") (pintype "bidirectional"))
      (node (ref "U$12") (pin "14") (pinfunction "VSS_14") (pintype "bidirectional"))
      (node (ref "U$12") (pin "24") (pinfunction "A5_24") (pintype "bidirectional"))
      (node (ref "U$12") (pin "25") (pinfunction "EXTCLK_25") (pintype "bidirectional"))
      (node (ref "U$12") (pin "3") (pinfunction "A2_3") (pintype "bidirectional"))
      (node (ref "U$12") (pin "4") (pinfunction "A3_4") (pintype "bidirectional"))
      (node (ref "U$12") (pin "5") (pinfunction "A4_5") (pintype "bidirectional"))
      (node (ref "U$13") (pin "1") (pinfunction "S1_1") (pintype "input"))
      (node (ref "U$13") (pin "3") (pinfunction "S2_3") (pintype "bidirectional"))
      (node (ref "U$14") (pin "1") (pinfunction "S1_1") (pintype "input"))
      (node (ref "U$14") (pin "3") (pinfunction "S2_3") (pintype "bidirectional"))
      (node (ref "U$15") (pin "1") (pinfunction "S1_1") (pintype "input"))
      (node (ref "U$15") (pin "3") (pinfunction "S2_3") (pintype "bidirectional"))
      (node (ref "U$16") (pin "1") (pinfunction "S1_1") (pintype "input"))
      (node (ref "U$16") (pin "3") (pinfunction "S2_3") (pintype "bidirectional"))
      (node (ref "U$17") (pin "1") (pinfunction "S1_1") (pintype "input"))
      (node (ref "U$17") (pin "3") (pinfunction "S2_3") (pintype "bidirectional"))
      (node (ref "U$18") (pin "1") (pinfunction "S1_1") (pintype "input"))
      (node (ref "U$18") (pin "3") (pinfunction "S2_3") (pintype "bidirectional"))
      (node (ref "U$19") (pin "1") (pinfunction "S1_1") (pintype "input"))
      (node (ref "U$19") (pin "3") (pinfunction "S2_3") (pintype "bidirectional"))
      (node (ref "U$2") (pin "14") (pinfunction "VSS_14") (pintype "bidirectional"))
      (node (ref "U$2") (pin "2") (pinfunction "A1_2") (pintype "bidirectional"))
      (node (ref "U$2") (pin "24") (pinfunction "A5_24") (pintype "bidirectional"))
      (node (ref "U$2") (pin "25") (pinfunction "EXTCLK_25") (pintype "bidirectional"))
      (node (ref "U$2") (pin "3") (pinfunction "A2_3") (pintype "bidirectional"))
      (node (ref "U$2") (pin "4") (pinfunction "A3_4") (pintype "bidirectional"))
      (node (ref "U$2") (pin "5") (pinfunction "A4_5") (pintype "bidirectional"))
      (node (ref "U$20") (pin "1") (pinfunction "S1_1") (pintype "input"))
      (node (ref "U$20") (pin "3") (pinfunction "S2_3") (pintype "bidirectional"))
      (node (ref "U$21") (pin "14") (pinfunction "VSS_14") (pintype "bidirectional"))
      (node (ref "U$21") (pin "24") (pinfunction "A5_24") (pintype "bidirectional"))
      (node (ref "U$21") (pin "25") (pinfunction "EXTCLK_25") (pintype "bidirectional"))
      (node (ref "U$21") (pin "4") (pinfunction "A3_4") (pintype "bidirectional"))
      (node (ref "U$21") (pin "5") (pinfunction "A4_5") (pintype "bidirectional"))
      (node (ref "U$22") (pin "1") (pinfunction "S1_1") (pintype "input"))
      (node (ref "U$22") (pin "3") (pinfunction "S2_3") (pintype "bidirectional"))
      (node (ref "U$23") (pin "1") (pinfunction "S1_1") (pintype "input"))
      (node (ref "U$23") (pin "3") (pinfunction "S2_3") (pintype "bidirectional"))
      (node (ref "U$24") (pin "1") (pinfunction "S1_1") (pintype "input"))
      (node (ref "U$24") (pin "3") (pinfunction "S2_3") (pintype "bidirectional"))
      (node (ref "U$25") (pin "1") (pinfunction "S1_1") (pintype "input"))
      (node (ref "U$25") (pin "3") (pinfunction "S2_3") (pintype "bidirectional"))
      (node (ref "U$26") (pin "1") (pinfunction "S1_1") (pintype "input"))
      (node (ref "U$26") (pin "3") (pinfunction "S2_3") (pintype "bidirectional"))
      (node (ref "U$27") (pin "1") (pinfunction "S1_1") (pintype "input"))
      (node (ref "U$27") (pin "3") (pinfunction "S2_3") (pintype "bidirectional"))
      (node (ref "U$28") (pin "1") (pinfunction "S1_1") (pintype "input"))
      (node (ref "U$28") (pin "3") (pinfunction "S2_3") (pintype "bidirectional"))
      (node (ref "U$3") (pin "5") (pinfunction "GND_5") (pintype "bidirectional"))
      (node (ref "U$4") (pin "1") (pinfunction "S1_1") (pintype "input"))
      (node (ref "U$4") (pin "3") (pinfunction "S2_3") (pintype "bidirectional"))
      (node (ref "U$5") (pin "1") (pinfunction "S1_1") (pintype "input"))
      (node (ref "U$5") (pin "3") (pinfunction "S2_3") (pintype "bidirectional"))
      (node (ref "U$6") (pin "1") (pinfunction "S1_1") (pintype "input"))
      (node (ref "U$6") (pin "3") (pinfunction "S2_3") (pintype "bidirectional"))
      (node (ref "U$7") (pin "1") (pinfunction "S1_1") (pintype "input"))
      (node (ref "U$7") (pin "3") (pinfunction "S2_3") (pintype "bidirectional"))
      (node (ref "U$8") (pin "1") (pinfunction "S1_1") (pintype "input"))
      (node (ref "U$8") (pin "3") (pinfunction "S2_3") (pintype "bidirectional"))
      (node (ref "U$9") (pin "1") (pinfunction "S1_1") (pintype "input"))
      (node (ref "U$9") (pin "3") (pinfunction "S2_3") (pintype "bidirectional"))
    )
    (net (code "7") (name "Net-(IC1-(PCI0{slash}ICP{slash}CLKO)PB0)") (class "Default")
      (node (ref "IC1") (pin "12") (pinfunction "(PCI0/ICP/CLKO)PB0_12") (pintype "bidirectional"))
      (node (ref "R6") (pin "1") (pinfunction "1_1") (pintype "passive"))
    )
    (net (code "8") (name "Net-(IC1-(PCI1{slash}OC1A{slash}OC1S)PB1)") (class "Default")
      (node (ref "IC1") (pin "13") (pinfunction "(PCI1/OC1A/OC1S)PB1_13") (pintype "bidirectional"))
      (node (ref "R7") (pin "1") (pinfunction "1_1") (pintype "passive"))
    )
    (net (code "9") (name "Net-(IC1-(PCI2{slash}SS{slash}OC1B)PB2)") (class "Default")
      (node (ref "IC1") (pin "14") (pinfunction "(PCI2/SS/OC1B)PB2_14") (pintype "bidirectional"))
      (node (ref "R8") (pin "1") (pinfunction "1_1") (pintype "passive"))
    )
    (net (code "10") (name "Net-(IC1-(PCI3{slash}MOSI{slash}OC2A)PB3)") (class "Default")
      (node (ref "IC1") (pin "15") (pinfunction "(PCI3/MOSI/OC2A)PB3_15") (pintype "bidirectional"))
      (node (ref "JP1") (pin "1") (pinfunction "1_1") (pintype "passive"))
    )
    (net (code "11") (name "Net-(IC1-(PCI4{slash}MISO)PB4)") (class "Default")
      (node (ref "IC1") (pin "16") (pinfunction "(PCI4/MISO)PB4_16") (pintype "bidirectional"))
      (node (ref "JP1") (pin "9") (pinfunction "9_9") (pintype "passive"))
    )
    (net (code "12") (name "Net-(IC1-(PCI5{slash}SCK)PB5)") (class "Default")
      (node (ref "IC1") (pin "17") (pinfunction "(PCI5/SCK)PB5_17") (pintype "bidirectional"))
      (node (ref "JP1") (pin "7") (pinfunction "7_7") (pintype "passive"))
    )
    (net (code "13") (name "Net-(IC1-(PCI8{slash}ADC0)PC0)") (class "Default")
      (node (ref "IC1") (pin "23") (pinfunction "(PCI8/ADC0)PC0_23") (pintype "bidirectional"))
      (node (ref "SJ1") (pin "1") (pinfunction "1_1") (pintype "passive"))
    )
    (net (code "14") (name "Net-(IC1-(PCI9{slash}ADC1)PC1)") (class "Default")
      (node (ref "IC1") (pin "24") (pinfunction "(PCI9/ADC1)PC1_24") (pintype "bidirectional"))
      (node (ref "SJ2") (pin "1") (pinfunction "1_1") (pintype "passive"))
    )
    (net (code "15") (name "Net-(IC1-(PCI10{slash}ADC2)PC2)") (class "Default")
      (node (ref "IC1") (pin "25") (pinfunction "(PCI10/ADC2)PC2_25") (pintype "bidirectional"))
      (node (ref "SJ3") (pin "1") (pinfunction "1_1") (pintype "passive"))
    )
    (net (code "16") (name "Net-(IC1-(PCI11{slash}ADC3)PC3)") (class "Default")
      (node (ref "IC1") (pin "26") (pinfunction "(PCI11/ADC3)PC3_26") (pintype "bidirectional"))
      (node (ref "SJ4") (pin "1") (pinfunction "1_1") (pintype "passive"))
    )
    (net (code "17") (name "Net-(IC1-(PCI16{slash}RXD)PD0)") (class "Default")
      (node (ref "IC1") (pin "30") (pinfunction "(PCI16/RXD)PD0_30") (pintype "bidirectional"))
      (node (ref "U$3") (pin "1") (pinfunction "R_1") (pintype "output"))
    )
    (net (code "18") (name "Net-(IC1-(PCI17{slash}TXD)PD1)") (class "Default")
      (node (ref "IC1") (pin "31") (pinfunction "(PCI17/TXD)PD1_31") (pintype "bidirectional"))
      (node (ref "U$3") (pin "4") (pinfunction "D_4") (pintype "input"))
    )
    (net (code "19") (name "Net-(IC1-(PCI18{slash}INT0)PD2)") (class "Default")
      (node (ref "IC1") (pin "32") (pinfunction "(PCI18/INT0)PD2_32") (pintype "bidirectional"))
      (node (ref "R4") (pin "2") (pinfunction "2_2") (pintype "passive"))
      (node (ref "U$3") (pin "2") (pinfunction "RE_2") (pintype "input"))
      (node (ref "U$3") (pin "3") (pinfunction "DE_3") (pintype "input"))
    )
    (net (code "20") (name "Net-(IC1-(PCI20{slash}XCK{slash}T0)PD4)") (class "Default")
      (node (ref "IC1") (pin "2") (pinfunction "(PCI20/XCK/T0)PD4_2") (pintype "bidirectional"))
      (node (ref "SJ5") (pin "1") (pinfunction "1_1") (pintype "passive"))
    )
    (net (code "21") (name "Net-(IC1-(PCI21{slash}T1{slash}OC0B)PD5)") (class "Default")
      (node (ref "IC1") (pin "9") (pinfunction "(PCI21/T1/OC0B)PD5_9") (pintype "bidirectional"))
      (node (ref "SJ6") (pin "1") (pinfunction "1_1") (pintype "passive"))
    )
    (net (code "22") (name "Net-(IC1-(PCI22{slash}AIN0OC0A)PD6)") (class "Default")
      (node (ref "IC1") (pin "10") (pinfunction "(PCI22/AIN0OC0A)PD6_10") (pintype "bidirectional"))
      (node (ref "SJ7") (pin "1") (pinfunction "1_1") (pintype "passive"))
    )
    (net (code "23") (name "Net-(IC1-(PCI23{slash}AIN1)PD7)") (class "Default")
      (node (ref "IC1") (pin "11") (pinfunction "(PCI23/AIN1)PD7_11") (pintype "bidirectional"))
      (node (ref "SJ8") (pin "1") (pinfunction "1_1") (pintype "passive"))
    )
    (net (code "24") (name "Net-(IC1-PB6(XTAL1{slash}TOSC1{slash}PCI6))") (class "Default")
      (node (ref "C4") (pin "1") (pinfunction "1_1") (pintype "passive"))
      (node (ref "IC1") (pin "7") (pinfunction "PB6(XTAL1/TOSC1/PCI6)_7") (pintype "bidirectional"))
      (node (ref "Q1") (pin "1") (pinfunction "1_1") (pintype "passive"))
    )
    (net (code "25") (name "Net-(IC1-PB7(XTAL2{slash}TOSC2{slash}PCI7))") (class "Default")
      (node (ref "C5") (pin "1") (pinfunction "1_1") (pintype "passive"))
      (node (ref "IC1") (pin "8") (pinfunction "PB7(XTAL2/TOSC2/PCI7)_8") (pintype "bidirectional"))
      (node (ref "Q1") (pin "2") (pinfunction "2_2") (pintype "passive"))
    )
    (net (code "26") (name "Net-(IC1-PC6({slash}RESET{slash}PCI14))") (class "Default")
      (node (ref "IC1") (pin "29") (pinfunction "PC6(/RESET/PCI14)_29") (pintype "bidirectional"))
      (node (ref "JP1") (pin "5") (pinfunction "5_5") (pintype "passive"))
      (node (ref "R1") (pin "1") (pinfunction "1_1") (pintype "passive"))
    )
    (net (code "27") (name "Net-(LED1-PadC)") (class "Default")
      (node (ref "LED1") (pin "C") (pinfunction "C_C") (pintype "passive"))
      (node (ref "R6") (pin "2") (pinfunction "2_2") (pintype "passive"))
    )
    (net (code "28") (name "Net-(LED2-PadC)") (class "Default")
      (node (ref "LED2") (pin "C") (pinfunction "C_C") (pintype "passive"))
      (node (ref "R7") (pin "2") (pinfunction "2_2") (pintype "passive"))
    )
    (net (code "29") (name "Net-(LED3-PadC)") (class "Default")
      (node (ref "LED3") (pin "C") (pinfunction "C_C") (pintype "passive"))
      (node (ref "R8") (pin "2") (pinfunction "2_2") (pintype "passive"))
    )
    (net (code "30") (name "Net-(PAD1-P)") (class "Default")
      (node (ref "PAD1") (pin "P$1") (pinfunction "P_P$1") (pintype "passive"))
      (node (ref "U$1") (pin "7") (pinfunction "D1B_7") (pintype "bidirectional"))
      (node (ref "U$1") (pin "8") (pinfunction "D1A_8") (pintype "bidirectional"))
    )
    (net (code "31") (name "Net-(PAD2-P)") (class "Default")
      (node (ref "PAD2") (pin "P$1") (pinfunction "P_P$1") (pintype "passive"))
      (node (ref "U$1") (pin "5") (pinfunction "D2B_5") (pintype "bidirectional"))
      (node (ref "U$1") (pin "6") (pinfunction "D2A_6") (pintype "bidirectional"))
    )
    (net (code "32") (name "Net-(PAD3-P)") (class "Default")
      (node (ref "PAD3") (pin "P$1") (pinfunction "P_P$1") (pintype "passive"))
      (node (ref "U$4") (pin "7") (pinfunction "D1B_7") (pintype "bidirectional"))
      (node (ref "U$4") (pin "8") (pinfunction "D1A_8") (pintype "bidirectional"))
    )
    (net (code "33") (name "Net-(PAD4-P)") (class "Default")
      (node (ref "PAD4") (pin "P$1") (pinfunction "P_P$1") (pintype "passive"))
      (node (ref "U$4") (pin "5") (pinfunction "D2B_5") (pintype "bidirectional"))
      (node (ref "U$4") (pin "6") (pinfunction "D2A_6") (pintype "bidirectional"))
    )
    (net (code "34") (name "Net-(PAD5-P)") (class "Default")
      (node (ref "PAD5") (pin "P$1") (pinfunction "P_P$1") (pintype "passive"))
      (node (ref "U$5") (pin "7") (pinfunction "D1B_7") (pintype "bidirectional"))
      (node (ref "U$5") (pin "8") (pinfunction "D1A_8") (pintype "bidirectional"))
    )
    (net (code "35") (name "Net-(PAD6-P)") (class "Default")
      (node (ref "PAD6") (pin "P$1") (pinfunction "P_P$1") (pintype "passive"))
      (node (ref "U$5") (pin "5") (pinfunction "D2B_5") (pintype "bidirectional"))
      (node (ref "U$5") (pin "6") (pinfunction "D2A_6") (pintype "bidirectional"))
    )
    (net (code "36") (name "Net-(PAD7-P)") (class "Default")
      (node (ref "PAD7") (pin "P$1") (pinfunction "P_P$1") (pintype "passive"))
      (node (ref "U$6") (pin "7") (pinfunction "D1B_7") (pintype "bidirectional"))
      (node (ref "U$6") (pin "8") (pinfunction "D1A_8") (pintype "bidirectional"))
    )
    (net (code "37") (name "Net-(PAD8-P)") (class "Default")
      (node (ref "PAD8") (pin "P$1") (pinfunction "P_P$1") (pintype "passive"))
      (node (ref "U$6") (pin "5") (pinfunction "D2B_5") (pintype "bidirectional"))
      (node (ref "U$6") (pin "6") (pinfunction "D2A_6") (pintype "bidirectional"))
    )
    (net (code "38") (name "Net-(PAD9-P)") (class "Default")
      (node (ref "PAD9") (pin "P$1") (pinfunction "P_P$1") (pintype "passive"))
      (node (ref "U$7") (pin "7") (pinfunction "D1B_7") (pintype "bidirectional"))
      (node (ref "U$7") (pin "8") (pinfunction "D1A_8") (pintype "bidirectional"))
    )
    (net (code "39") (name "Net-(PAD10-P)") (class "Default")
      (node (ref "PAD10") (pin "P$1") (pinfunction "P_P$1") (pintype "passive"))
      (node (ref "U$7") (pin "5") (pinfunction "D2B_5") (pintype "bidirectional"))
      (node (ref "U$7") (pin "6") (pinfunction "D2A_6") (pintype "bidirectional"))
    )
    (net (code "40") (name "Net-(PAD11-P)") (class "Default")
      (node (ref "PAD11") (pin "P$1") (pinfunction "P_P$1") (pintype "passive"))
      (node (ref "U$8") (pin "7") (pinfunction "D1B_7") (pintype "bidirectional"))
      (node (ref "U$8") (pin "8") (pinfunction "D1A_8") (pintype "bidirectional"))
    )
    (net (code "41") (name "Net-(PAD12-P)") (class "Default")
      (node (ref "PAD12") (pin "P$1") (pinfunction "P_P$1") (pintype "passive"))
      (node (ref "U$8") (pin "5") (pinfunction "D2B_5") (pintype "bidirectional"))
      (node (ref "U$8") (pin "6") (pinfunction "D2A_6") (pintype "bidirectional"))
    )
    (net (code "42") (name "Net-(PAD13-P)") (class "Default")
      (node (ref "PAD13") (pin "P$1") (pinfunction "P_P$1") (pintype "passive"))
      (node (ref "U$9") (pin "7") (pinfunction "D1B_7") (pintype "bidirectional"))
      (node (ref "U$9") (pin "8") (pinfunction "D1A_8") (pintype "bidirectional"))
    )
    (net (code "43") (name "Net-(PAD14-P)") (class "Default")
      (node (ref "PAD14") (pin "P$1") (pinfunction "P_P$1") (pintype "passive"))
      (node (ref "U$9") (pin "5") (pinfunction "D2B_5") (pintype "bidirectional"))
      (node (ref "U$9") (pin "6") (pinfunction "D2A_6") (pintype "bidirectional"))
    )
    (net (code "44") (name "Net-(PAD15-P)") (class "Default")
      (node (ref "PAD15") (pin "P$1") (pinfunction "P_P$1") (pintype "passive"))
      (node (ref "U$10") (pin "7") (pinfunction "D1B_7") (pintype "bidirectional"))
      (node (ref "U$10") (pin "8") (pinfunction "D1A_8") (pintype "bidirectional"))
    )
    (net (code "45") (name "Net-(PAD16-P)") (class "Default")
      (node (ref "PAD16") (pin "P$1") (pinfunction "P_P$1") (pintype "passive"))
      (node (ref "U$10") (pin "5") (pinfunction "D2B_5") (pintype "bidirectional"))
      (node (ref "U$10") (pin "6") (pinfunction "D2A_6") (pintype "bidirectional"))
    )
    (net (code "46") (name "Net-(PAD17-P)") (class "Default")
      (node (ref "PAD17") (pin "P$1") (pinfunction "P_P$1") (pintype "passive"))
      (node (ref "U$11") (pin "7") (pinfunction "D1B_7") (pintype "bidirectional"))
      (node (ref "U$11") (pin "8") (pinfunction "D1A_8") (pintype "bidirectional"))
    )
    (net (code "47") (name "Net-(PAD18-P)") (class "Default")
      (node (ref "PAD18") (pin "P$1") (pinfunction "P_P$1") (pintype "passive"))
      (node (ref "U$11") (pin "5") (pinfunction "D2B_5") (pintype "bidirectional"))
      (node (ref "U$11") (pin "6") (pinfunction "D2A_6") (pintype "bidirectional"))
    )
    (net (code "48") (name "Net-(PAD19-P)") (class "Default")
      (node (ref "PAD19") (pin "P$1") (pinfunction "P_P$1") (pintype "passive"))
      (node (ref "U$13") (pin "7") (pinfunction "D1B_7") (pintype "bidirectional"))
      (node (ref "U$13") (pin "8") (pinfunction "D1A_8") (pintype "bidirectional"))
    )
    (net (code "49") (name "Net-(PAD20-P)") (class "Default")
      (node (ref "PAD20") (pin "P$1") (pinfunction "P_P$1") (pintype "passive"))
      (node (ref "U$13") (pin "5") (pinfunction "D2B_5") (pintype "bidirectional"))
      (node (ref "U$13") (pin "6") (pinfunction "D2A_6") (pintype "bidirectional"))
    )
    (net (code "50") (name "Net-(PAD21-P)") (class "Default")
      (node (ref "PAD21") (pin "P$1") (pinfunction "P_P$1") (pintype "passive"))
      (node (ref "U$14") (pin "7") (pinfunction "D1B_7") (pintype "bidirectional"))
      (node (ref "U$14") (pin "8") (pinfunction "D1A_8") (pintype "bidirectional"))
    )
    (net (code "51") (name "Net-(PAD22-P)") (class "Default")
      (node (ref "PAD22") (pin "P$1") (pinfunction "P_P$1") (pintype "passive"))
      (node (ref "U$14") (pin "5") (pinfunction "D2B_5") (pintype "bidirectional"))
      (node (ref "U$14") (pin "6") (pinfunction "D2A_6") (pintype "bidirectional"))
    )
    (net (code "52") (name "Net-(PAD23-P)") (class "Default")
      (node (ref "PAD23") (pin "P$1") (pinfunction "P_P$1") (pintype "passive"))
      (node (ref "U$15") (pin "7") (pinfunction "D1B_7") (pintype "bidirectional"))
      (node (ref "U$15") (pin "8") (pinfunction "D1A_8") (pintype "bidirectional"))
    )
    (net (code "53") (name "Net-(PAD24-P)") (class "Default")
      (node (ref "PAD24") (pin "P$1") (pinfunction "P_P$1") (pintype "passive"))
      (node (ref "U$15") (pin "5") (pinfunction "D2B_5") (pintype "bidirectional"))
      (node (ref "U$15") (pin "6") (pinfunction "D2A_6") (pintype "bidirectional"))
    )
    (net (code "54") (name "Net-(PAD25-P)") (class "Default")
      (node (ref "PAD25") (pin "P$1") (pinfunction "P_P$1") (pintype "passive"))
      (node (ref "U$16") (pin "7") (pinfunction "D1B_7") (pintype "bidirectional"))
      (node (ref "U$16") (pin "8") (pinfunction "D1A_8") (pintype "bidirectional"))
    )
    (net (code "55") (name "Net-(PAD26-P)") (class "Default")
      (node (ref "PAD26") (pin "P$1") (pinfunction "P_P$1") (pintype "passive"))
      (node (ref "U$16") (pin "5") (pinfunction "D2B_5") (pintype "bidirectional"))
      (node (ref "U$16") (pin "6") (pinfunction "D2A_6") (pintype "bidirectional"))
    )
    (net (code "56") (name "Net-(PAD27-P)") (class "Default")
      (node (ref "PAD27") (pin "P$1") (pinfunction "P_P$1") (pintype "passive"))
      (node (ref "U$17") (pin "7") (pinfunction "D1B_7") (pintype "bidirectional"))
      (node (ref "U$17") (pin "8") (pinfunction "D1A_8") (pintype "bidirectional"))
    )
    (net (code "57") (name "Net-(PAD28-P)") (class "Default")
      (node (ref "PAD28") (pin "P$1") (pinfunction "P_P$1") (pintype "passive"))
      (node (ref "U$17") (pin "5") (pinfunction "D2B_5") (pintype "bidirectional"))
      (node (ref "U$17") (pin "6") (pinfunction "D2A_6") (pintype "bidirectional"))
    )
    (net (code "58") (name "Net-(PAD29-P)") (class "Default")
      (node (ref "PAD29") (pin "P$1") (pinfunction "P_P$1") (pintype "passive"))
      (node (ref "U$18") (pin "7") (pinfunction "D1B_7") (pintype "bidirectional"))
      (node (ref "U$18") (pin "8") (pinfunction "D1A_8") (pintype "bidirectional"))
    )
    (net (code "59") (name "Net-(PAD30-P)") (class "Default")
      (node (ref "PAD30") (pin "P$1") (pinfunction "P_P$1") (pintype "passive"))
      (node (ref "U$18") (pin "5") (pinfunction "D2B_5") (pintype "bidirectional"))
      (node (ref "U$18") (pin "6") (pinfunction "D2A_6") (pintype "bidirectional"))
    )
    (net (code "60") (name "Net-(PAD31-P)") (class "Default")
      (node (ref "PAD31") (pin "P$1") (pinfunction "P_P$1") (pintype "passive"))
      (node (ref "U$19") (pin "7") (pinfunction "D1B_7") (pintype "bidirectional"))
      (node (ref "U$19") (pin "8") (pinfunction "D1A_8") (pintype "bidirectional"))
    )
    (net (code "61") (name "Net-(PAD32-P)") (class "Default")
      (node (ref "PAD32") (pin "P$1") (pinfunction "P_P$1") (pintype "passive"))
      (node (ref "U$19") (pin "5") (pinfunction "D2B_5") (pintype "bidirectional"))
      (node (ref "U$19") (pin "6") (pinfunction "D2A_6") (pintype "bidirectional"))
    )
    (net (code "62") (name "Net-(PAD33-P)") (class "Default")
      (node (ref "PAD33") (pin "P$1") (pinfunction "P_P$1") (pintype "passive"))
      (node (ref "U$20") (pin "7") (pinfunction "D1B_7") (pintype "bidirectional"))
      (node (ref "U$20") (pin "8") (pinfunction "D1A_8") (pintype "bidirectional"))
    )
    (net (code "63") (name "Net-(PAD34-P)") (class "Default")
      (node (ref "PAD34") (pin "P$1") (pinfunction "P_P$1") (pintype "passive"))
      (node (ref "U$20") (pin "5") (pinfunction "D2B_5") (pintype "bidirectional"))
      (node (ref "U$20") (pin "6") (pinfunction "D2A_6") (pintype "bidirectional"))
    )
    (net (code "64") (name "Net-(PAD35-P)") (class "Default")
      (node (ref "PAD35") (pin "P$1") (pinfunction "P_P$1") (pintype "passive"))
      (node (ref "U$22") (pin "7") (pinfunction "D1B_7") (pintype "bidirectional"))
      (node (ref "U$22") (pin "8") (pinfunction "D1A_8") (pintype "bidirectional"))
    )
    (net (code "65") (name "Net-(PAD36-P)") (class "Default")
      (node (ref "PAD36") (pin "P$1") (pinfunction "P_P$1") (pintype "passive"))
      (node (ref "U$22") (pin "5") (pinfunction "D2B_5") (pintype "bidirectional"))
      (node (ref "U$22") (pin "6") (pinfunction "D2A_6") (pintype "bidirectional"))
    )
    (net (code "66") (name "Net-(PAD37-P)") (class "Default")
      (node (ref "PAD37") (pin "P$1") (pinfunction "P_P$1") (pintype "passive"))
      (node (ref "U$23") (pin "7") (pinfunction "D1B_7") (pintype "bidirectional"))
      (node (ref "U$23") (pin "8") (pinfunction "D1A_8") (pintype "bidirectional"))
    )
    (net (code "67") (name "Net-(PAD38-P)") (class "Default")
      (node (ref "PAD38") (pin "P$1") (pinfunction "P_P$1") (pintype "passive"))
      (node (ref "U$23") (pin "5") (pinfunction "D2B_5") (pintype "bidirectional"))
      (node (ref "U$23") (pin "6") (pinfunction "D2A_6") (pintype "bidirectional"))
    )
    (net (code "68") (name "Net-(PAD39-P)") (class "Default")
      (node (ref "PAD39") (pin "P$1") (pinfunction "P_P$1") (pintype "passive"))
      (node (ref "U$24") (pin "7") (pinfunction "D1B_7") (pintype "bidirectional"))
      (node (ref "U$24") (pin "8") (pinfunction "D1A_8") (pintype "bidirectional"))
    )
    (net (code "69") (name "Net-(PAD40-P)") (class "Default")
      (node (ref "PAD40") (pin "P$1") (pinfunction "P_P$1") (pintype "passive"))
      (node (ref "U$24") (pin "5") (pinfunction "D2B_5") (pintype "bidirectional"))
      (node (ref "U$24") (pin "6") (pinfunction "D2A_6") (pintype "bidirectional"))
    )
    (net (code "70") (name "Net-(PAD41-P)") (class "Default")
      (node (ref "PAD41") (pin "P$1") (pinfunction "P_P$1") (pintype "passive"))
      (node (ref "U$25") (pin "7") (pinfunction "D1B_7") (pintype "bidirectional"))
      (node (ref "U$25") (pin "8") (pinfunction "D1A_8") (pintype "bidirectional"))
    )
    (net (code "71") (name "Net-(PAD42-P)") (class "Default")
      (node (ref "PAD42") (pin "P$1") (pinfunction "P_P$1") (pintype "passive"))
      (node (ref "U$25") (pin "5") (pinfunction "D2B_5") (pintype "bidirectional"))
      (node (ref "U$25") (pin "6") (pinfunction "D2A_6") (pintype "bidirectional"))
    )
    (net (code "72") (name "Net-(PAD43-P)") (class "Default")
      (node (ref "PAD43") (pin "P$1") (pinfunction "P_P$1") (pintype "passive"))
      (node (ref "U$26") (pin "7") (pinfunction "D1B_7") (pintype "bidirectional"))
      (node (ref "U$26") (pin "8") (pinfunction "D1A_8") (pintype "bidirectional"))
    )
    (net (code "73") (name "Net-(PAD44-P)") (class "Default")
      (node (ref "PAD44") (pin "P$1") (pinfunction "P_P$1") (pintype "passive"))
      (node (ref "U$26") (pin "5") (pinfunction "D2B_5") (pintype "bidirectional"))
      (node (ref "U$26") (pin "6") (pinfunction "D2A_6") (pintype "bidirectional"))
    )
    (net (code "74") (name "Net-(PAD45-P)") (class "Default")
      (node (ref "PAD45") (pin "P$1") (pinfunction "P_P$1") (pintype "passive"))
      (node (ref "U$27") (pin "7") (pinfunction "D1B_7") (pintype "bidirectional"))
      (node (ref "U$27") (pin "8") (pinfunction "D1A_8") (pintype "bidirectional"))
    )
    (net (code "75") (name "Net-(PAD46-P)") (class "Default")
      (node (ref "PAD46") (pin "P$1") (pinfunction "P_P$1") (pintype "passive"))
      (node (ref "U$27") (pin "5") (pinfunction "D2B_5") (pintype "bidirectional"))
      (node (ref "U$27") (pin "6") (pinfunction "D2A_6") (pintype "bidirectional"))
    )
    (net (code "76") (name "Net-(PAD47-P)") (class "Default")
      (node (ref "PAD47") (pin "P$1") (pinfunction "P_P$1") (pintype "passive"))
      (node (ref "U$28") (pin "7") (pinfunction "D1B_7") (pintype "bidirectional"))
      (node (ref "U$28") (pin "8") (pinfunction "D1A_8") (pintype "bidirectional"))
    )
    (net (code "77") (name "Net-(PAD48-P)") (class "Default")
      (node (ref "PAD48") (pin "P$1") (pinfunction "P_P$1") (pintype "passive"))
      (node (ref "U$28") (pin "5") (pinfunction "D2B_5") (pintype "bidirectional"))
      (node (ref "U$28") (pin "6") (pinfunction "D2A_6") (pintype "bidirectional"))
    )
    (net (code "78") (name "Net-(PAD99-P)") (class "Default")
      (node (ref "PAD99") (pin "P$1") (pinfunction "P_P$1") (pintype "passive"))
      (node (ref "U$3") (pin "7") (pinfunction "B_7") (pintype "bidirectional"))
    )
    (net (code "79") (name "Net-(PAD100-P)") (class "Default")
      (node (ref "PAD100") (pin "P$1") (pinfunction "P_P$1") (pintype "passive"))
      (node (ref "U$3") (pin "6") (pinfunction "A_6") (pintype "bidirectional"))
    )
    (net (code "80") (name "Net-(U$1-G1)") (class "Default")
      (node (ref "U$1") (pin "2") (pinfunction "G1_2") (pintype "bidirectional"))
      (node (ref "U$2") (pin "13") (pinfunction "LED7_13") (pintype "output"))
    )
    (net (code "81") (name "Net-(U$1-G2)") (class "Default")
      (node (ref "U$1") (pin "4") (pinfunction "G2_4") (pintype "input"))
      (node (ref "U$2") (pin "12") (pinfunction "LED6_12") (pintype "output"))
    )
    (net (code "82") (name "Net-(U$2-LED0)") (class "Default")
      (node (ref "U$2") (pin "6") (pinfunction "LED0_6") (pintype "output"))
      (node (ref "U$6") (pin "4") (pinfunction "G2_4") (pintype "input"))
    )
    (net (code "83") (name "Net-(U$2-LED1)") (class "Default")
      (node (ref "U$2") (pin "7") (pinfunction "LED1_7") (pintype "output"))
      (node (ref "U$6") (pin "2") (pinfunction "G1_2") (pintype "bidirectional"))
    )
    (net (code "84") (name "Net-(U$2-LED2)") (class "Default")
      (node (ref "U$2") (pin "8") (pinfunction "LED2_8") (pintype "output"))
      (node (ref "U$5") (pin "4") (pinfunction "G2_4") (pintype "input"))
    )
    (net (code "85") (name "Net-(U$2-LED3)") (class "Default")
      (node (ref "U$2") (pin "9") (pinfunction "LED3_9") (pintype "output"))
      (node (ref "U$5") (pin "2") (pinfunction "G1_2") (pintype "bidirectional"))
    )
    (net (code "86") (name "Net-(U$2-LED4)") (class "Default")
      (node (ref "U$2") (pin "10") (pinfunction "LED4_10") (pintype "output"))
      (node (ref "U$4") (pin "4") (pinfunction "G2_4") (pintype "input"))
    )
    (net (code "87") (name "Net-(U$2-LED5)") (class "Default")
      (node (ref "U$2") (pin "11") (pinfunction "LED5_11") (pintype "output"))
      (node (ref "U$4") (pin "2") (pinfunction "G1_2") (pintype "bidirectional"))
    )
    (net (code "88") (name "Net-(U$2-LED8)") (class "Default")
      (node (ref "U$2") (pin "15") (pinfunction "LED8_15") (pintype "output"))
      (node (ref "U$7") (pin "2") (pinfunction "G1_2") (pintype "bidirectional"))
    )
    (net (code "89") (name "Net-(U$2-LED9)") (class "Default")
      (node (ref "U$2") (pin "16") (pinfunction "LED9_16") (pintype "output"))
      (node (ref "U$7") (pin "4") (pinfunction "G2_4") (pintype "input"))
    )
    (net (code "90") (name "Net-(U$2-LED10)") (class "Default")
      (node (ref "U$2") (pin "17") (pinfunction "LED10_17") (pintype "output"))
      (node (ref "U$8") (pin "2") (pinfunction "G1_2") (pintype "bidirectional"))
    )
    (net (code "91") (name "Net-(U$2-LED11)") (class "Default")
      (node (ref "U$2") (pin "18") (pinfunction "LED11_18") (pintype "output"))
      (node (ref "U$8") (pin "4") (pinfunction "G2_4") (pintype "input"))
    )
    (net (code "92") (name "Net-(U$2-LED12)") (class "Default")
      (node (ref "U$2") (pin "19") (pinfunction "LED12_19") (pintype "output"))
      (node (ref "U$9") (pin "2") (pinfunction "G1_2") (pintype "bidirectional"))
    )
    (net (code "93") (name "Net-(U$2-LED13)") (class "Default")
      (node (ref "U$2") (pin "20") (pinfunction "LED13_20") (pintype "output"))
      (node (ref "U$9") (pin "4") (pinfunction "G2_4") (pintype "input"))
    )
    (net (code "94") (name "Net-(U$10-G1)") (class "Default")
      (node (ref "U$10") (pin "2") (pinfunction "G1_2") (pintype "bidirectional"))
      (node (ref "U$2") (pin "21") (pinfunction "LED14_21") (pintype "output"))
    )
    (net (code "95") (name "Net-(U$10-G2)") (class "Default")
      (node (ref "U$10") (pin "4") (pinfunction "G2_4") (pintype "input"))
      (node (ref "U$2") (pin "22") (pinfunction "LED15_22") (pintype "output"))
    )
    (net (code "96") (name "Net-(U$11-G1)") (class "Default")
      (node (ref "U$11") (pin "2") (pinfunction "G1_2") (pintype "bidirectional"))
      (node (ref "U$12") (pin "13") (pinfunction "LED7_13") (pintype "output"))
    )
    (net (code "97") (name "Net-(U$11-G2)") (class "Default")
      (node (ref "U$11") (pin "4") (pinfunction "G2_4") (pintype "input"))
      (node (ref "U$12") (pin "12") (pinfunction "LED6_12") (pintype "output"))
    )
    (net (code "98") (name "Net-(U$12-LED0)") (class "Default")
      (node (ref "U$12") (pin "6") (pinfunction "LED0_6") (pintype "output"))
      (node (ref "U$15") (pin "4") (pinfunction "G2_4") (pintype "input"))
    )
    (net (code "99") (name "Net-(U$12-LED1)") (class "Default")
      (node (ref "U$12") (pin "7") (pinfunction "LED1_7") (pintype "output"))
      (node (ref "U$15") (pin "2") (pinfunction "G1_2") (pintype "bidirectional"))
    )
    (net (code "100") (name "Net-(U$12-LED2)") (class "Default")
      (node (ref "U$12") (pin "8") (pinfunction "LED2_8") (pintype "output"))
      (node (ref "U$14") (pin "4") (pinfunction "G2_4") (pintype "input"))
    )
    (net (code "101") (name "Net-(U$12-LED3)") (class "Default")
      (node (ref "U$12") (pin "9") (pinfunction "LED3_9") (pintype "output"))
      (node (ref "U$14") (pin "2") (pinfunction "G1_2") (pintype "bidirectional"))
    )
    (net (code "102") (name "Net-(U$12-LED4)") (class "Default")
      (node (ref "U$12") (pin "10") (pinfunction "LED4_10") (pintype "output"))
      (node (ref "U$13") (pin "4") (pinfunction "G2_4") (pintype "input"))
    )
    (net (code "103") (name "Net-(U$12-LED5)") (class "Default")
      (node (ref "U$12") (pin "11") (pinfunction "LED5_11") (pintype "output"))
      (node (ref "U$13") (pin "2") (pinfunction "G1_2") (pintype "bidirectional"))
    )
    (net (code "104") (name "Net-(U$12-LED8)") (class "Default")
      (node (ref "U$12") (pin "15") (pinfunction "LED8_15") (pintype "output"))
      (node (ref "U$16") (pin "2") (pinfunction "G1_2") (pintype "bidirectional"))
    )
    (net (code "105") (name "Net-(U$12-LED9)") (class "Default")
      (node (ref "U$12") (pin "16") (pinfunction "LED9_16") (pintype "output"))
      (node (ref "U$16") (pin "4") (pinfunction "G2_4") (pintype "input"))
    )
    (net (code "106") (name "Net-(U$12-LED10)") (class "Default")
      (node (ref "U$12") (pin "17") (pinfunction "LED10_17") (pintype "output"))
      (node (ref "U$17") (pin "2") (pinfunction "G1_2") (pintype "bidirectional"))
    )
    (net (code "107") (name "Net-(U$12-LED11)") (class "Default")
      (node (ref "U$12") (pin "18") (pinfunction "LED11_18") (pintype "output"))
      (node (ref "U$17") (pin "4") (pinfunction "G2_4") (pintype "input"))
    )
    (net (code "108") (name "Net-(U$12-LED12)") (class "Default")
      (node (ref "U$12") (pin "19") (pinfunction "LED12_19") (pintype "output"))
      (node (ref "U$18") (pin "2") (pinfunction "G1_2") (pintype "bidirectional"))
    )
    (net (code "109") (name "Net-(U$12-LED13)") (class "Default")
      (node (ref "U$12") (pin "20") (pinfunction "LED13_20") (pintype "output"))
      (node (ref "U$18") (pin "4") (pinfunction "G2_4") (pintype "input"))
    )
    (net (code "110") (name "Net-(U$12-LED14)") (class "Default")
      (node (ref "U$12") (pin "21") (pinfunction "LED14_21") (pintype "output"))
      (node (ref "U$19") (pin "2") (pinfunction "G1_2") (pintype "bidirectional"))
    )
    (net (code "111") (name "Net-(U$12-LED15)") (class "Default")
      (node (ref "U$12") (pin "22") (pinfunction "LED15_22") (pintype "output"))
      (node (ref "U$19") (pin "4") (pinfunction "G2_4") (pintype "input"))
    )
    (net (code "112") (name "Net-(U$20-G1)") (class "Default")
      (node (ref "U$20") (pin "2") (pinfunction "G1_2") (pintype "bidirectional"))
      (node (ref "U$21") (pin "13") (pinfunction "LED7_13") (pintype "output"))
    )
    (net (code "113") (name "Net-(U$20-G2)") (class "Default")
      (node (ref "U$20") (pin "4") (pinfunction "G2_4") (pintype "input"))
      (node (ref "U$21") (pin "12") (pinfunction "LED6_12") (pintype "output"))
    )
    (net (code "114") (name "Net-(U$21-LED0)") (class "Default")
      (node (ref "U$21") (pin "6") (pinfunction "LED0_6") (pintype "output"))
      (node (ref "U$24") (pin "4") (pinfunction "G2_4") (pintype "input"))
    )
    (net (code "115") (name "Net-(U$21-LED1)") (class "Default")
      (node (ref "U$21") (pin "7") (pinfunction "LED1_7") (pintype "output"))
      (node (ref "U$24") (pin "2") (pinfunction "G1_2") (pintype "bidirectional"))
    )
    (net (code "116") (name "Net-(U$21-LED2)") (class "Default")
      (node (ref "U$21") (pin "8") (pinfunction "LED2_8") (pintype "output"))
      (node (ref "U$23") (pin "4") (pinfunction "G2_4") (pintype "input"))
    )
    (net (code "117") (name "Net-(U$21-LED3)") (class "Default")
      (node (ref "U$21") (pin "9") (pinfunction "LED3_9") (pintype "output"))
      (node (ref "U$23") (pin "2") (pinfunction "G1_2") (pintype "bidirectional"))
    )
    (net (code "118") (name "Net-(U$21-LED4)") (class "Default")
      (node (ref "U$21") (pin "10") (pinfunction "LED4_10") (pintype "output"))
      (node (ref "U$22") (pin "4") (pinfunction "G2_4") (pintype "input"))
    )
    (net (code "119") (name "Net-(U$21-LED5)") (class "Default")
      (node (ref "U$21") (pin "11") (pinfunction "LED5_11") (pintype "output"))
      (node (ref "U$22") (pin "2") (pinfunction "G1_2") (pintype "bidirectional"))
    )
    (net (code "120") (name "Net-(U$21-LED8)") (class "Default")
      (node (ref "U$21") (pin "15") (pinfunction "LED8_15") (pintype "output"))
      (node (ref "U$25") (pin "2") (pinfunction "G1_2") (pintype "bidirectional"))
    )
    (net (code "121") (name "Net-(U$21-LED9)") (class "Default")
      (node (ref "U$21") (pin "16") (pinfunction "LED9_16") (pintype "output"))
      (node (ref "U$25") (pin "4") (pinfunction "G2_4") (pintype "input"))
    )
    (net (code "122") (name "Net-(U$21-LED10)") (class "Default")
      (node (ref "U$21") (pin "17") (pinfunction "LED10_17") (pintype "output"))
      (node (ref "U$26") (pin "2") (pinfunction "G1_2") (pintype "bidirectional"))
    )
    (net (code "123") (name "Net-(U$21-LED11)") (class "Default")
      (node (ref "U$21") (pin "18") (pinfunction "LED11_18") (pintype "output"))
      (node (ref "U$26") (pin "4") (pinfunction "G2_4") (pintype "input"))
    )
    (net (code "124") (name "Net-(U$21-LED12)") (class "Default")
      (node (ref "U$21") (pin "19") (pinfunction "LED12_19") (pintype "output"))
      (node (ref "U$27") (pin "2") (pinfunction "G1_2") (pintype "bidirectional"))
    )
    (net (code "125") (name "Net-(U$21-LED13)") (class "Default")
      (node (ref "U$21") (pin "20") (pinfunction "LED13_20") (pintype "output"))
      (node (ref "U$27") (pin "4") (pinfunction "G2_4") (pintype "input"))
    )
    (net (code "126") (name "Net-(U$21-LED14)") (class "Default")
      (node (ref "U$21") (pin "21") (pinfunction "LED14_21") (pintype "output"))
      (node (ref "U$28") (pin "2") (pinfunction "G1_2") (pintype "bidirectional"))
    )
    (net (code "127") (name "Net-(U$21-LED15)") (class "Default")
      (node (ref "U$21") (pin "22") (pinfunction "LED15_22") (pintype "output"))
      (node (ref "U$28") (pin "4") (pinfunction "G2_4") (pintype "input"))
    )
    (net (code "128") (name "unconnected-(IC1-ADC6-Pad19)") (class "Default")
      (node (ref "IC1") (pin "19") (pinfunction "ADC6_19") (pintype "bidirectional"))
    )
    (net (code "129") (name "unconnected-(IC1-ADC7-Pad22)") (class "Default")
      (node (ref "IC1") (pin "22") (pinfunction "ADC7_22") (pintype "bidirectional"))
    )
  )
)
